# my_dac_amp_vB.net
KiCad netlist of a schematic drawn in EAGLE
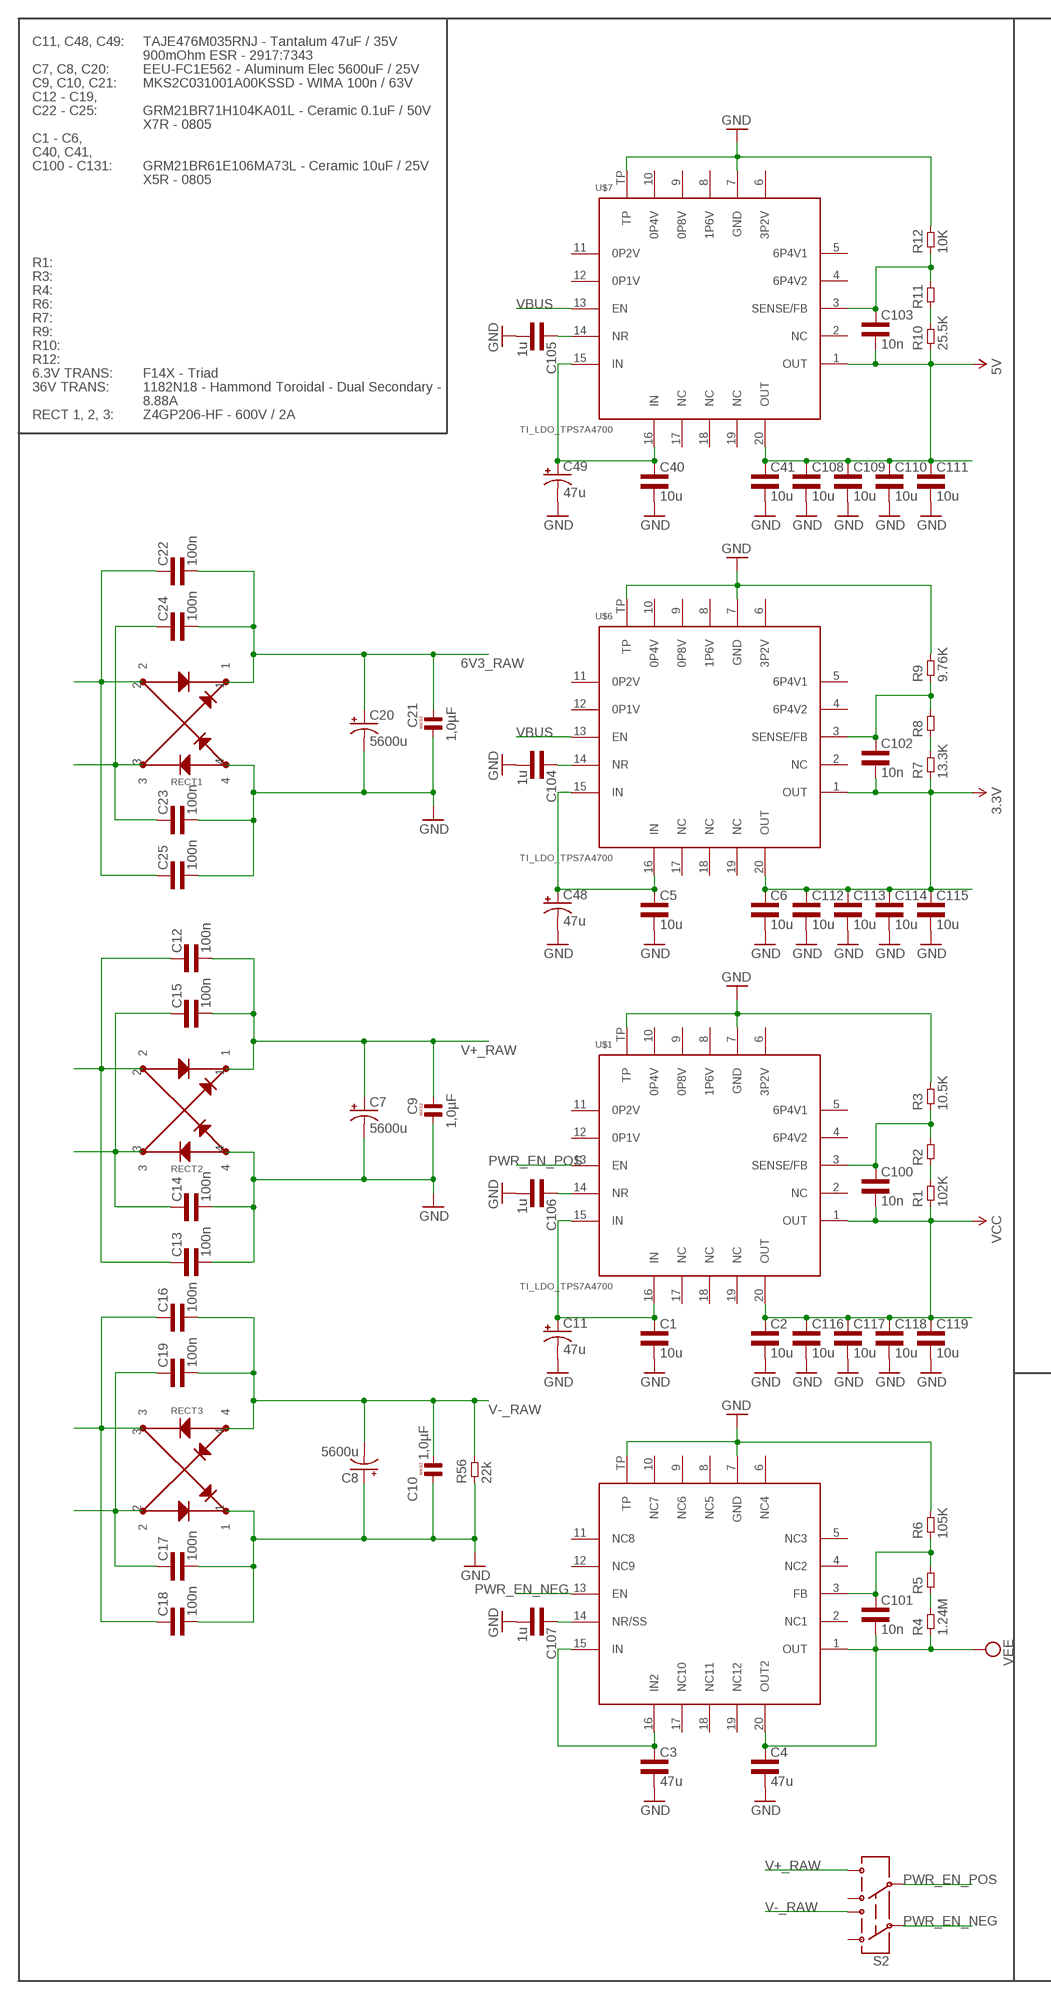
[diagram p0: schematic, sheet 1, part 1 of 2]
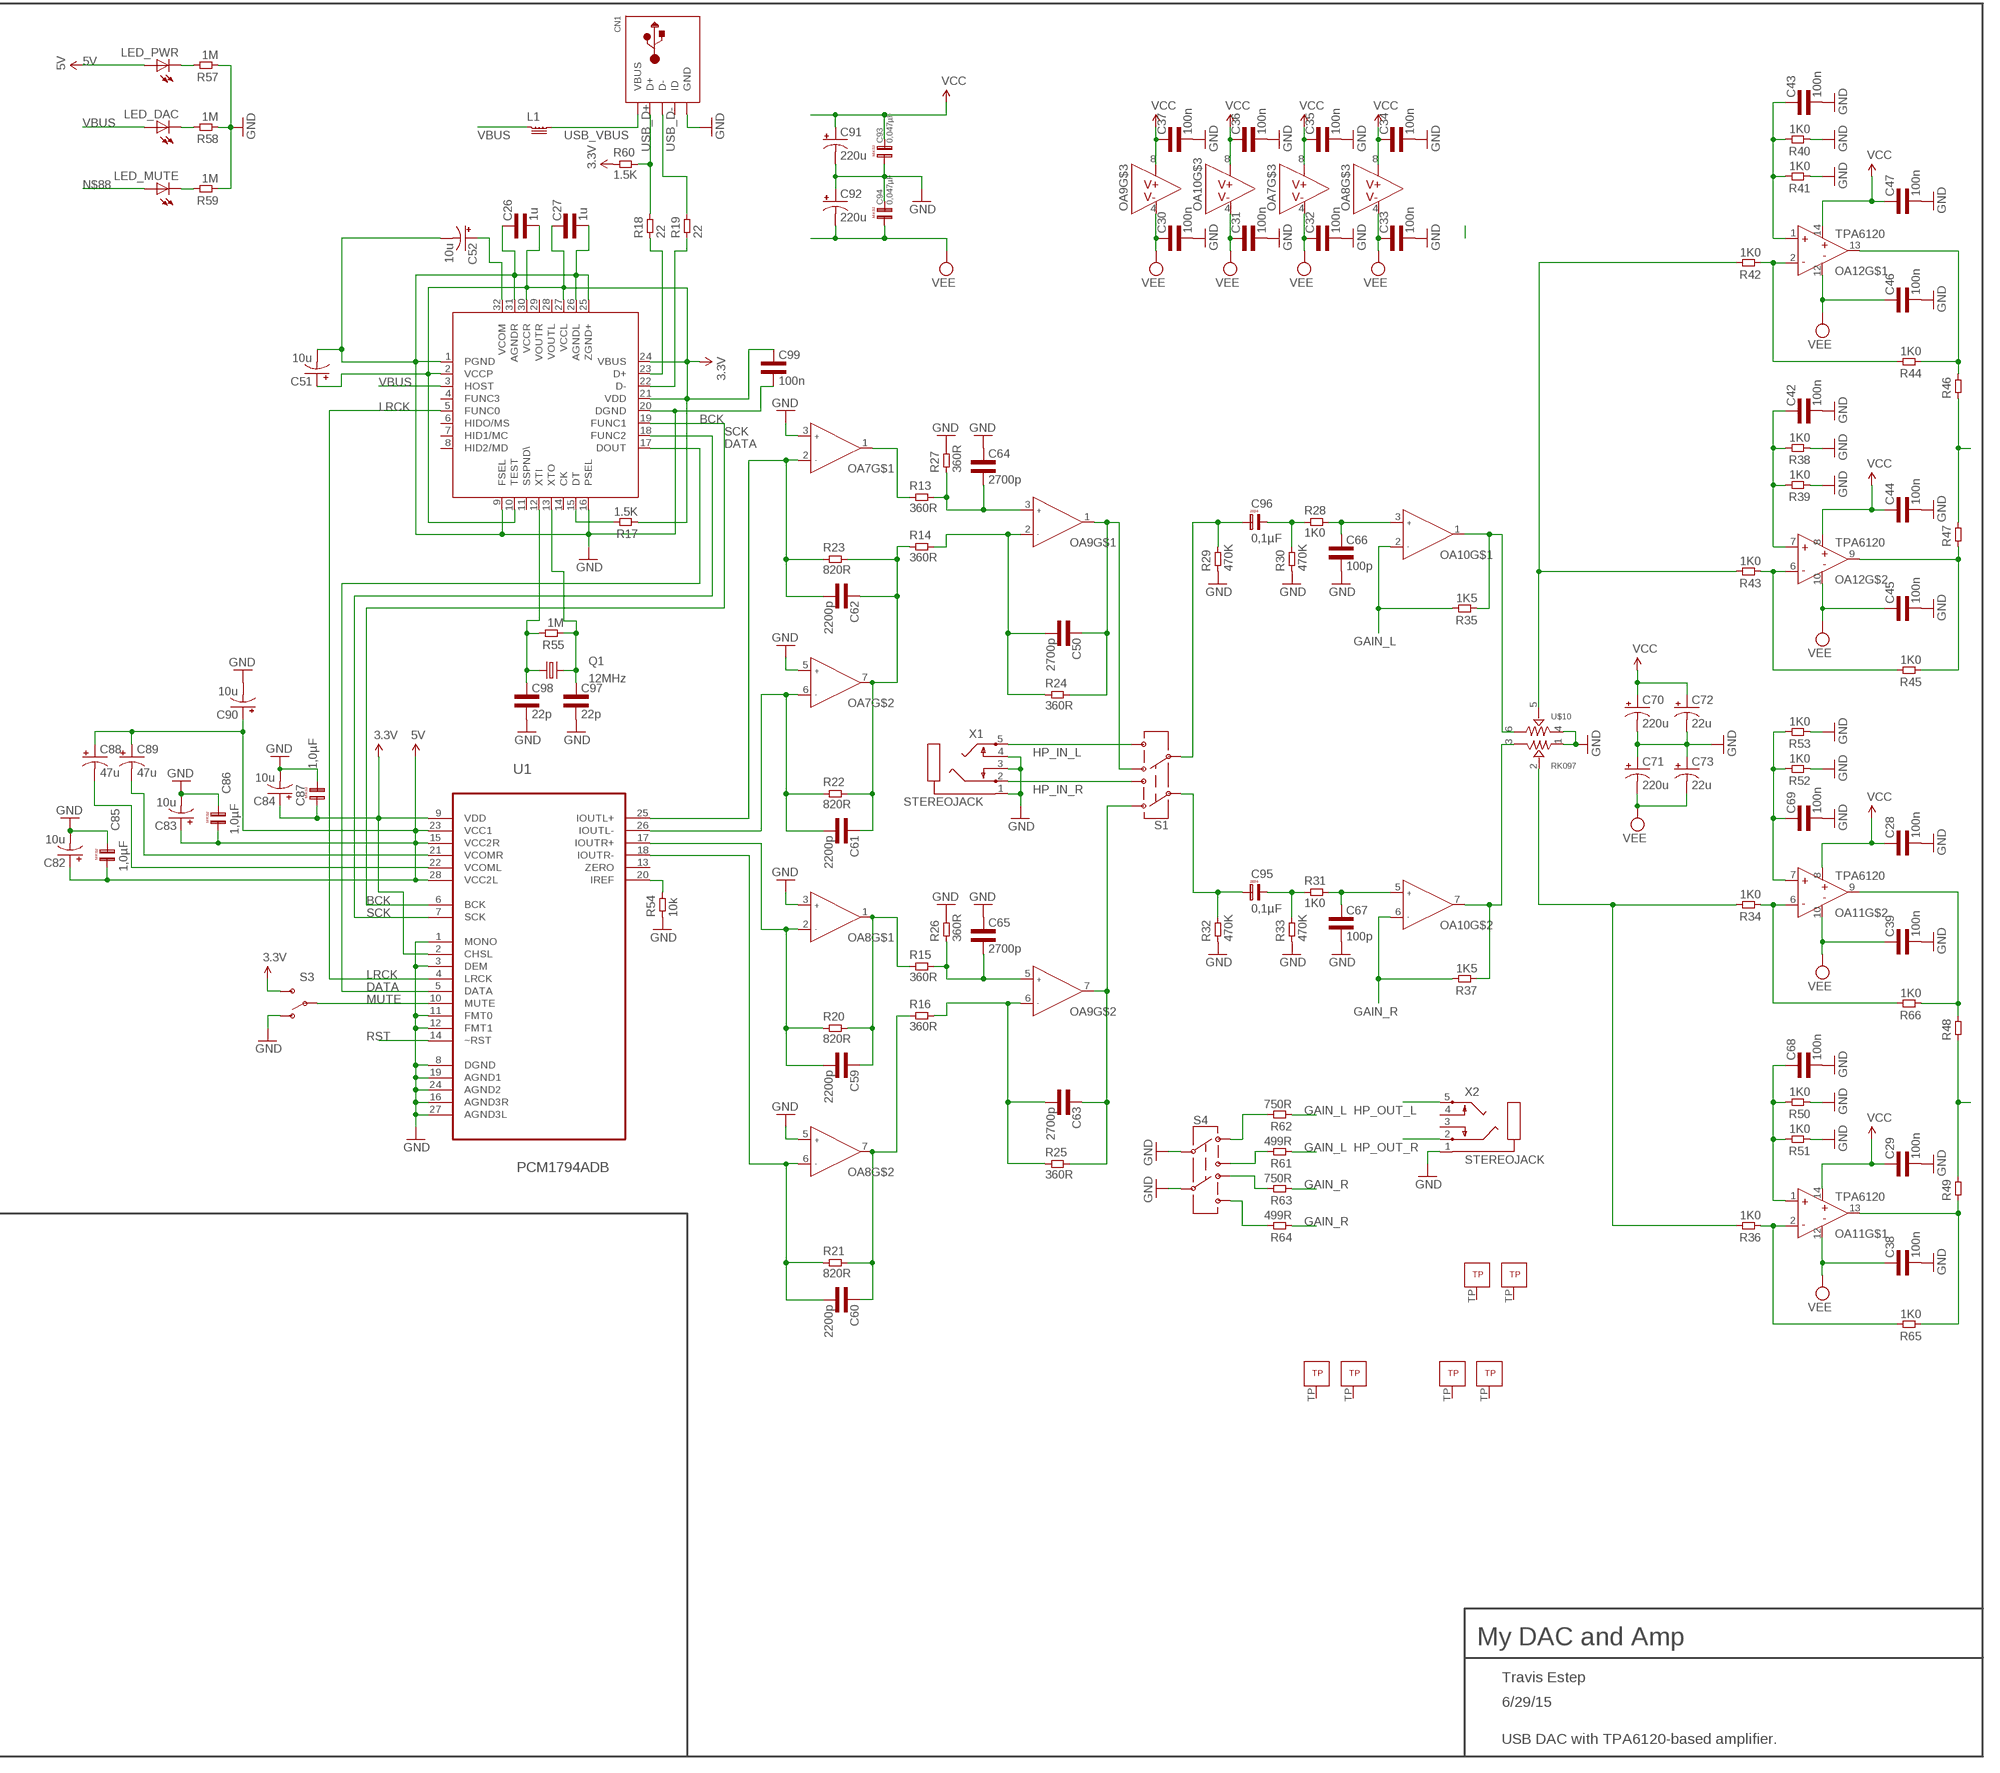
[diagram p1: schematic, sheet 1, part 2 of 2]

(export (version "E")
  (design (tool "Eeschema 10.0.6"))
  (components
    (comp (ref "C1")
      (value "10u")
      (footprint "eagle-import:1206L3")
      (libsource (lib "eagle-import") (part "CAP1206L3"))
    )
    (comp (ref "C2")
      (value "10u")
      (footprint "eagle-import:0805L3")
      (libsource (lib "eagle-import") (part "CAP0805L3"))
    )
    (comp (ref "C3")
      (value "47u")
      (footprint "eagle-import:1206L3")
      (libsource (lib "eagle-import") (part "CAP1206L3"))
    )
    (comp (ref "C4")
      (value "47u")
      (footprint "eagle-import:1206L3")
      (libsource (lib "eagle-import") (part "CAP1206L3"))
    )
    (comp (ref "C5")
      (value "10u")
      (footprint "eagle-import:1206L3")
      (libsource (lib "eagle-import") (part "CAP1206L3"))
    )
    (comp (ref "C6")
      (value "10u")
      (footprint "eagle-import:0805L3")
      (libsource (lib "eagle-import") (part "CAP0805L3"))
    )
    (comp (ref "C7")
      (value "5600u")
      (footprint "eagle-import:E7,5-16")
      (libsource (lib "eagle-import") (part "CPOL-USE7.5-16"))
    )
    (comp (ref "C8")
      (value "5600u")
      (footprint "eagle-import:E7,5-16")
      (libsource (lib "eagle-import") (part "CPOL-USE7.5-16"))
    )
    (comp (ref "C9")
      (value "1,0µF")
      (footprint "eagle-import:R5B5")
      (libsource (lib "eagle-import") (part "Capacitor-Wima-MKS2-63v_1,0µF"))
    )
    (comp (ref "C10")
      (value "1,0µF")
      (footprint "eagle-import:R5B5")
      (libsource (lib "eagle-import") (part "Capacitor-Wima-MKS2-63v_1,0µF"))
    )
    (comp (ref "C11")
      (value "47u")
      (footprint "eagle-import:SMC_E")
      (libsource (lib "eagle-import") (part "CPOL-USSMCE"))
    )
    (comp (ref "C12")
      (value "100n")
      (footprint "eagle-import:0805L3")
      (libsource (lib "eagle-import") (part "CAP0805L3"))
    )
    (comp (ref "C13")
      (value "100n")
      (footprint "eagle-import:0805L3")
      (libsource (lib "eagle-import") (part "CAP0805L3"))
    )
    (comp (ref "C14")
      (value "100n")
      (footprint "eagle-import:0805L3")
      (libsource (lib "eagle-import") (part "CAP0805L3"))
    )
    (comp (ref "C15")
      (value "100n")
      (footprint "eagle-import:0805L3")
      (libsource (lib "eagle-import") (part "CAP0805L3"))
    )
    (comp (ref "C16")
      (value "100n")
      (footprint "eagle-import:0805L3")
      (libsource (lib "eagle-import") (part "CAP0805L3"))
    )
    (comp (ref "C17")
      (value "100n")
      (footprint "eagle-import:0805L3")
      (libsource (lib "eagle-import") (part "CAP0805L3"))
    )
    (comp (ref "C18")
      (value "100n")
      (footprint "eagle-import:0805L3")
      (libsource (lib "eagle-import") (part "CAP0805L3"))
    )
    (comp (ref "C19")
      (value "100n")
      (footprint "eagle-import:0805L3")
      (libsource (lib "eagle-import") (part "CAP0805L3"))
    )
    (comp (ref "C20")
      (value "5600u")
      (footprint "eagle-import:E7,5-16")
      (libsource (lib "eagle-import") (part "CPOL-USE7.5-16"))
    )
    (comp (ref "C21")
      (value "1,0µF")
      (footprint "eagle-import:R5B5")
      (libsource (lib "eagle-import") (part "Capacitor-Wima-MKS2-63v_1,0µF"))
    )
    (comp (ref "C22")
      (value "100n")
      (footprint "eagle-import:0805L3")
      (libsource (lib "eagle-import") (part "CAP0805L3"))
    )
    (comp (ref "C23")
      (value "100n")
      (footprint "eagle-import:0805L3")
      (libsource (lib "eagle-import") (part "CAP0805L3"))
    )
    (comp (ref "C24")
      (value "100n")
      (footprint "eagle-import:0805L3")
      (libsource (lib "eagle-import") (part "CAP0805L3"))
    )
    (comp (ref "C25")
      (value "100n")
      (footprint "eagle-import:0805L3")
      (libsource (lib "eagle-import") (part "CAP0805L3"))
    )
    (comp (ref "C26")
      (value "1u")
      (footprint "eagle-import:0603L3")
      (libsource (lib "eagle-import") (part "CAP0603L3"))
    )
    (comp (ref "C27")
      (value "1u")
      (footprint "eagle-import:0603L3")
      (libsource (lib "eagle-import") (part "CAP0603L3"))
    )
    (comp (ref "C28")
      (value "100n")
      (footprint "eagle-import:0603L3")
      (libsource (lib "eagle-import") (part "CAP0603L3"))
    )
    (comp (ref "C29")
      (value "100n")
      (footprint "eagle-import:0603L3")
      (libsource (lib "eagle-import") (part "CAP0603L3"))
    )
    (comp (ref "C30")
      (value "100n")
      (footprint "eagle-import:0603L3")
      (libsource (lib "eagle-import") (part "CAP0603L3"))
    )
    (comp (ref "C31")
      (value "100n")
      (footprint "eagle-import:0603L3")
      (libsource (lib "eagle-import") (part "CAP0603L3"))
    )
    (comp (ref "C32")
      (value "100n")
      (footprint "eagle-import:0603L3")
      (libsource (lib "eagle-import") (part "CAP0603L3"))
    )
    (comp (ref "C33")
      (value "100n")
      (footprint "eagle-import:0603L3")
      (libsource (lib "eagle-import") (part "CAP0603L3"))
    )
    (comp (ref "C34")
      (value "100n")
      (footprint "eagle-import:0603L3")
      (libsource (lib "eagle-import") (part "CAP0603L3"))
    )
    (comp (ref "C35")
      (value "100n")
      (footprint "eagle-import:0603L3")
      (libsource (lib "eagle-import") (part "CAP0603L3"))
    )
    (comp (ref "C36")
      (value "100n")
      (footprint "eagle-import:0603L3")
      (libsource (lib "eagle-import") (part "CAP0603L3"))
    )
    (comp (ref "C37")
      (value "100n")
      (footprint "eagle-import:0603L3")
      (libsource (lib "eagle-import") (part "CAP0603L3"))
    )
    (comp (ref "C38")
      (value "100n")
      (footprint "eagle-import:0603L3")
      (libsource (lib "eagle-import") (part "CAP0603L3"))
    )
    (comp (ref "C39")
      (value "100n")
      (footprint "eagle-import:0603L3")
      (libsource (lib "eagle-import") (part "CAP0603L3"))
    )
    (comp (ref "C40")
      (value "10u")
      (footprint "eagle-import:1206L3")
      (libsource (lib "eagle-import") (part "CAP1206L3"))
    )
    (comp (ref "C41")
      (value "10u")
      (footprint "eagle-import:0805L3")
      (libsource (lib "eagle-import") (part "CAP0805L3"))
    )
    (comp (ref "C42")
      (value "100n")
      (footprint "eagle-import:0603L3")
      (libsource (lib "eagle-import") (part "CAP0603L3"))
    )
    (comp (ref "C43")
      (value "100n")
      (footprint "eagle-import:0603L3")
      (libsource (lib "eagle-import") (part "CAP0603L3"))
    )
    (comp (ref "C44")
      (value "100n")
      (footprint "eagle-import:0603L3")
      (libsource (lib "eagle-import") (part "CAP0603L3"))
    )
    (comp (ref "C45")
      (value "100n")
      (footprint "eagle-import:0603L3")
      (libsource (lib "eagle-import") (part "CAP0603L3"))
    )
    (comp (ref "C46")
      (value "100n")
      (footprint "eagle-import:0603L3")
      (libsource (lib "eagle-import") (part "CAP0603L3"))
    )
    (comp (ref "C47")
      (value "100n")
      (footprint "eagle-import:0603L3")
      (libsource (lib "eagle-import") (part "CAP0603L3"))
    )
    (comp (ref "C48")
      (value "47u")
      (footprint "eagle-import:SMC_E")
      (libsource (lib "eagle-import") (part "CPOL-USSMCE"))
    )
    (comp (ref "C49")
      (value "47u")
      (footprint "eagle-import:SMC_E")
      (libsource (lib "eagle-import") (part "CPOL-USSMCE"))
    )
    (comp (ref "C50")
      (value "2700p")
      (footprint "eagle-import:0603L3")
      (libsource (lib "eagle-import") (part "CAP0603L3"))
    )
    (comp (ref "C51")
      (value "10u")
      (footprint "eagle-import:E3,5-8")
      (libsource (lib "eagle-import") (part "CPOL-USE3.5-8"))
    )
    (comp (ref "C52")
      (value "10u")
      (footprint "eagle-import:E3,5-8")
      (libsource (lib "eagle-import") (part "CPOL-USE3.5-8"))
    )
    (comp (ref "C59")
      (value "2200p")
      (footprint "eagle-import:0603L3")
      (libsource (lib "eagle-import") (part "CAP0603L3"))
    )
    (comp (ref "C60")
      (value "2200p")
      (footprint "eagle-import:0603L3")
      (libsource (lib "eagle-import") (part "CAP0603L3"))
    )
    (comp (ref "C61")
      (value "2200p")
      (footprint "eagle-import:0603L3")
      (libsource (lib "eagle-import") (part "CAP0603L3"))
    )
    (comp (ref "C62")
      (value "2200p")
      (footprint "eagle-import:0603L3")
      (libsource (lib "eagle-import") (part "CAP0603L3"))
    )
    (comp (ref "C63")
      (value "2700p")
      (footprint "eagle-import:0603L3")
      (libsource (lib "eagle-import") (part "CAP0603L3"))
    )
    (comp (ref "C64")
      (value "2700p")
      (footprint "eagle-import:0603L3")
      (libsource (lib "eagle-import") (part "CAP0603L3"))
    )
    (comp (ref "C65")
      (value "2700p")
      (footprint "eagle-import:0603L3")
      (libsource (lib "eagle-import") (part "CAP0603L3"))
    )
    (comp (ref "C66")
      (value "100p")
      (footprint "eagle-import:0603L3")
      (libsource (lib "eagle-import") (part "CAP0603L3"))
    )
    (comp (ref "C67")
      (value "100p")
      (footprint "eagle-import:0603L3")
      (libsource (lib "eagle-import") (part "CAP0603L3"))
    )
    (comp (ref "C68")
      (value "100n")
      (footprint "eagle-import:0603L3")
      (libsource (lib "eagle-import") (part "CAP0603L3"))
    )
    (comp (ref "C69")
      (value "100n")
      (footprint "eagle-import:0603L3")
      (libsource (lib "eagle-import") (part "CAP0603L3"))
    )
    (comp (ref "C70")
      (value "220u")
      (footprint "eagle-import:E5-13")
      (libsource (lib "eagle-import") (part "CPOL-USE5-13"))
    )
    (comp (ref "C71")
      (value "220u")
      (footprint "eagle-import:E5-13")
      (libsource (lib "eagle-import") (part "CPOL-USE5-13"))
    )
    (comp (ref "C72")
      (value "22u")
      (footprint "eagle-import:E3,5-8")
      (libsource (lib "eagle-import") (part "CPOL-USE3.5-8"))
    )
    (comp (ref "C73")
      (value "22u")
      (footprint "eagle-import:E3,5-8")
      (libsource (lib "eagle-import") (part "CPOL-USE3.5-8"))
    )
    (comp (ref "C82")
      (value "10u")
      (footprint "eagle-import:E3,5-8")
      (libsource (lib "eagle-import") (part "CPOL-USE3.5-8"))
    )
    (comp (ref "C83")
      (value "10u")
      (footprint "eagle-import:E3,5-8")
      (libsource (lib "eagle-import") (part "CPOL-USE3.5-8"))
    )
    (comp (ref "C84")
      (value "10u")
      (footprint "eagle-import:E3,5-8")
      (libsource (lib "eagle-import") (part "CPOL-USE3.5-8"))
    )
    (comp (ref "C85")
      (value "1,0µF")
      (footprint "eagle-import:R5B5")
      (libsource (lib "eagle-import") (part "1,0µF"))
    )
    (comp (ref "C86")
      (value "1,0µF")
      (footprint "eagle-import:R5B5")
      (libsource (lib "eagle-import") (part "1,0µF"))
    )
    (comp (ref "C87")
      (value "1,0µF")
      (footprint "eagle-import:R5B5")
      (libsource (lib "eagle-import") (part "1,0µF"))
    )
    (comp (ref "C88")
      (value "47u")
      (footprint "eagle-import:E5-10,5")
      (libsource (lib "eagle-import") (part "CPOL-USE5-10.5"))
    )
    (comp (ref "C89")
      (value "47u")
      (footprint "eagle-import:E5-10,5")
      (libsource (lib "eagle-import") (part "CPOL-USE5-10.5"))
    )
    (comp (ref "C90")
      (value "10u")
      (footprint "eagle-import:E3,5-8")
      (libsource (lib "eagle-import") (part "CPOL-USE3.5-8"))
    )
    (comp (ref "C91")
      (value "220u")
      (footprint "eagle-import:E5-13")
      (libsource (lib "eagle-import") (part "CPOL-USE5-13"))
    )
    (comp (ref "C92")
      (value "220u")
      (footprint "eagle-import:E5-13")
      (libsource (lib "eagle-import") (part "CPOL-USE5-13"))
    )
    (comp (ref "C93")
      (value "0,047µF")
      (footprint "eagle-import:R5B2K5")
      (libsource (lib "eagle-import") (part "0,047µF"))
    )
    (comp (ref "C94")
      (value "0,047µF")
      (footprint "eagle-import:R5B2K5")
      (libsource (lib "eagle-import") (part "0,047µF"))
    )
    (comp (ref "C95")
      (value "0,1µF")
      (footprint "eagle-import:L7,2")
      (libsource (lib "eagle-import") (part "0,1µF"))
    )
    (comp (ref "C96")
      (value "0,1µF")
      (footprint "eagle-import:L7,2")
      (libsource (lib "eagle-import") (part "0,1µF"))
    )
    (comp (ref "C97")
      (value "22p")
      (footprint "eagle-import:0603L3")
      (libsource (lib "eagle-import") (part "CAP0603L3"))
    )
    (comp (ref "C98")
      (value "22p")
      (footprint "eagle-import:0603L3")
      (libsource (lib "eagle-import") (part "CAP0603L3"))
    )
    (comp (ref "C99")
      (value "100n")
      (footprint "eagle-import:0603L3")
      (libsource (lib "eagle-import") (part "CAP0603L3"))
    )
    (comp (ref "C100")
      (value "10n")
      (footprint "eagle-import:0603L3")
      (libsource (lib "eagle-import") (part "CAP0603L3"))
    )
    (comp (ref "C101")
      (value "10n")
      (footprint "eagle-import:0603L3")
      (libsource (lib "eagle-import") (part "CAP0603L3"))
    )
    (comp (ref "C102")
      (value "10n")
      (footprint "eagle-import:0603L3")
      (libsource (lib "eagle-import") (part "CAP0603L3"))
    )
    (comp (ref "C103")
      (value "10n")
      (footprint "eagle-import:0603L3")
      (libsource (lib "eagle-import") (part "CAP0603L3"))
    )
    (comp (ref "C104")
      (value "1u")
      (footprint "eagle-import:0603L3")
      (libsource (lib "eagle-import") (part "CAP0603L3"))
    )
    (comp (ref "C105")
      (value "1u")
      (footprint "eagle-import:0603L3")
      (libsource (lib "eagle-import") (part "CAP0603L3"))
    )
    (comp (ref "C106")
      (value "1u")
      (footprint "eagle-import:0603L3")
      (libsource (lib "eagle-import") (part "CAP0603L3"))
    )
    (comp (ref "C107")
      (value "1u")
      (footprint "eagle-import:0603L3")
      (libsource (lib "eagle-import") (part "CAP0603L3"))
    )
    (comp (ref "C108")
      (value "10u")
      (footprint "eagle-import:0805L3")
      (libsource (lib "eagle-import") (part "CAP0805L3"))
    )
    (comp (ref "C109")
      (value "10u")
      (footprint "eagle-import:0805L3")
      (libsource (lib "eagle-import") (part "CAP0805L3"))
    )
    (comp (ref "C110")
      (value "10u")
      (footprint "eagle-import:0805L3")
      (libsource (lib "eagle-import") (part "CAP0805L3"))
    )
    (comp (ref "C111")
      (value "10u")
      (footprint "eagle-import:0805L3")
      (libsource (lib "eagle-import") (part "CAP0805L3"))
    )
    (comp (ref "C112")
      (value "10u")
      (footprint "eagle-import:0805L3")
      (libsource (lib "eagle-import") (part "CAP0805L3"))
    )
    (comp (ref "C113")
      (value "10u")
      (footprint "eagle-import:0805L3")
      (libsource (lib "eagle-import") (part "CAP0805L3"))
    )
    (comp (ref "C114")
      (value "10u")
      (footprint "eagle-import:0805L3")
      (libsource (lib "eagle-import") (part "CAP0805L3"))
    )
    (comp (ref "C115")
      (value "10u")
      (footprint "eagle-import:0805L3")
      (libsource (lib "eagle-import") (part "CAP0805L3"))
    )
    (comp (ref "C116")
      (value "10u")
      (footprint "eagle-import:0805L3")
      (libsource (lib "eagle-import") (part "CAP0805L3"))
    )
    (comp (ref "C117")
      (value "10u")
      (footprint "eagle-import:0805L3")
      (libsource (lib "eagle-import") (part "CAP0805L3"))
    )
    (comp (ref "C118")
      (value "10u")
      (footprint "eagle-import:0805L3")
      (libsource (lib "eagle-import") (part "CAP0805L3"))
    )
    (comp (ref "C119")
      (value "10u")
      (footprint "eagle-import:0805L3")
      (libsource (lib "eagle-import") (part "CAP0805L3"))
    )
    (comp (ref "CN1")
      (value "USBMINIB")
      (footprint "eagle-import:USB-MINIB")
      (libsource (lib "eagle-import") (part "USBMINIB"))
    )
    (comp (ref "L1")
      (value "SRP4020")
      (footprint "eagle-import:4440")
      (libsource (lib "eagle-import") (part "SRP4020"))
    )
    (comp (ref "LED_DAC")
      (value "LED3MM")
      (footprint "eagle-import:LED3MM")
      (libsource (lib "eagle-import") (part "LED3MM"))
    )
    (comp (ref "LED_MUTE")
      (value "LED3MM")
      (footprint "eagle-import:LED3MM")
      (libsource (lib "eagle-import") (part "LED3MM"))
    )
    (comp (ref "LED_PWR")
      (value "LED3MM")
      (footprint "eagle-import:LED3MM")
      (libsource (lib "eagle-import") (part "LED3MM"))
    )
    (comp (ref "OA7")
      (value "OPA1612")
      (footprint "eagle-import:S-PWSON-N8")
      (libsource (lib "eagle-import") (part "OPA1612"))
    )
    (comp (ref "OA8")
      (value "OPA1612")
      (footprint "eagle-import:S-PWSON-N8")
      (libsource (lib "eagle-import") (part "OPA1612"))
    )
    (comp (ref "OA9")
      (value "OPA1612")
      (footprint "eagle-import:S-PWSON-N8")
      (libsource (lib "eagle-import") (part "OPA1612"))
    )
    (comp (ref "OA10")
      (value "OPA1612")
      (footprint "eagle-import:S-PWSON-N8")
      (libsource (lib "eagle-import") (part "OPA1612"))
    )
    (comp (ref "OA11")
      (value "TPA6120QFN")
      (footprint "eagle-import:S-PVQFN-N14")
      (libsource (lib "eagle-import") (part "TPA6120QFN"))
    )
    (comp (ref "OA12")
      (value "TPA6120QFN")
      (footprint "eagle-import:S-PVQFN-N14")
      (libsource (lib "eagle-import") (part "TPA6120QFN"))
    )
    (comp (ref "Q1")
      (value "12MHz")
      (footprint "eagle-import:SPARKFUN_HC49US")
      (libsource (lib "eagle-import") (part "SPARKFUN_CRYSTALHC49US"))
    )
    (comp (ref "R1")
      (value "102K")
      (footprint "eagle-import:0603L3")
      (libsource (lib "eagle-import") (part "RES0603L3"))
    )
    (comp (ref "R2")
      (value "RES0603L3")
      (footprint "eagle-import:0603L3")
      (libsource (lib "eagle-import") (part "RES0603L3"))
    )
    (comp (ref "R3")
      (value "10.5K")
      (footprint "eagle-import:0603L3")
      (libsource (lib "eagle-import") (part "RES0603L3"))
    )
    (comp (ref "R4")
      (value "1.24M")
      (footprint "eagle-import:0603L3")
      (libsource (lib "eagle-import") (part "RES0603L3"))
    )
    (comp (ref "R5")
      (value "RES0603L3")
      (footprint "eagle-import:0603L3")
      (libsource (lib "eagle-import") (part "RES0603L3"))
    )
    (comp (ref "R6")
      (value "105K")
      (footprint "eagle-import:0603L3")
      (libsource (lib "eagle-import") (part "RES0603L3"))
    )
    (comp (ref "R7")
      (value "13.3K")
      (footprint "eagle-import:0603L3")
      (libsource (lib "eagle-import") (part "RES0603L3"))
    )
    (comp (ref "R8")
      (value "RES0603L3")
      (footprint "eagle-import:0603L3")
      (libsource (lib "eagle-import") (part "RES0603L3"))
    )
    (comp (ref "R9")
      (value "9.76K")
      (footprint "eagle-import:0603L3")
      (libsource (lib "eagle-import") (part "RES0603L3"))
    )
    (comp (ref "R10")
      (value "25.5K")
      (footprint "eagle-import:0603L3")
      (libsource (lib "eagle-import") (part "RES0603L3"))
    )
    (comp (ref "R11")
      (value "RES0603L3")
      (footprint "eagle-import:0603L3")
      (libsource (lib "eagle-import") (part "RES0603L3"))
    )
    (comp (ref "R12")
      (value "10K")
      (footprint "eagle-import:0603L3")
      (libsource (lib "eagle-import") (part "RES0603L3"))
    )
    (comp (ref "R13")
      (value "360R")
      (footprint "eagle-import:0603L3")
      (libsource (lib "eagle-import") (part "RES0603L3"))
    )
    (comp (ref "R14")
      (value "360R")
      (footprint "eagle-import:0603L3")
      (libsource (lib "eagle-import") (part "RES0603L3"))
    )
    (comp (ref "R15")
      (value "360R")
      (footprint "eagle-import:0603L3")
      (libsource (lib "eagle-import") (part "RES0603L3"))
    )
    (comp (ref "R16")
      (value "360R")
      (footprint "eagle-import:0603L3")
      (libsource (lib "eagle-import") (part "RES0603L3"))
    )
    (comp (ref "R17")
      (value "1.5K")
      (footprint "eagle-import:0603L3")
      (libsource (lib "eagle-import") (part "RES0603L3"))
    )
    (comp (ref "R18")
      (value "22")
      (footprint "eagle-import:0603L3")
      (libsource (lib "eagle-import") (part "RES0603L3"))
    )
    (comp (ref "R19")
      (value "22")
      (footprint "eagle-import:0603L3")
      (libsource (lib "eagle-import") (part "RES0603L3"))
    )
    (comp (ref "R20")
      (value "820R")
      (footprint "eagle-import:0603L3")
      (libsource (lib "eagle-import") (part "RES0603L3"))
    )
    (comp (ref "R21")
      (value "820R")
      (footprint "eagle-import:0603L3")
      (libsource (lib "eagle-import") (part "RES0603L3"))
    )
    (comp (ref "R22")
      (value "820R")
      (footprint "eagle-import:0603L3")
      (libsource (lib "eagle-import") (part "RES0603L3"))
    )
    (comp (ref "R23")
      (value "820R")
      (footprint "eagle-import:0603L3")
      (libsource (lib "eagle-import") (part "RES0603L3"))
    )
    (comp (ref "R24")
      (value "360R")
      (footprint "eagle-import:0603L3")
      (libsource (lib "eagle-import") (part "RES0603L3"))
    )
    (comp (ref "R25")
      (value "360R")
      (footprint "eagle-import:0603L3")
      (libsource (lib "eagle-import") (part "RES0603L3"))
    )
    (comp (ref "R26")
      (value "360R")
      (footprint "eagle-import:0603L3")
      (libsource (lib "eagle-import") (part "RES0603L3"))
    )
    (comp (ref "R27")
      (value "360R")
      (footprint "eagle-import:0603L3")
      (libsource (lib "eagle-import") (part "RES0603L3"))
    )
    (comp (ref "R28")
      (value "1K0")
      (footprint "eagle-import:0603L3")
      (libsource (lib "eagle-import") (part "RES0603L3"))
    )
    (comp (ref "R29")
      (value "470K")
      (footprint "eagle-import:0603L3")
      (libsource (lib "eagle-import") (part "RES0603L3"))
    )
    (comp (ref "R30")
      (value "470K")
      (footprint "eagle-import:0603L3")
      (libsource (lib "eagle-import") (part "RES0603L3"))
    )
    (comp (ref "R31")
      (value "1K0")
      (footprint "eagle-import:0603L3")
      (libsource (lib "eagle-import") (part "RES0603L3"))
    )
    (comp (ref "R32")
      (value "470K")
      (footprint "eagle-import:0603L3")
      (libsource (lib "eagle-import") (part "RES0603L3"))
    )
    (comp (ref "R33")
      (value "470K")
      (footprint "eagle-import:0603L3")
      (libsource (lib "eagle-import") (part "RES0603L3"))
    )
    (comp (ref "R34")
      (value "1K0")
      (footprint "eagle-import:0603L3")
      (libsource (lib "eagle-import") (part "RES0603L3"))
    )
    (comp (ref "R35")
      (value "1K5")
      (footprint "eagle-import:0603L3")
      (libsource (lib "eagle-import") (part "RES0603L3"))
    )
    (comp (ref "R36")
      (value "1K0")
      (footprint "eagle-import:0603L3")
      (libsource (lib "eagle-import") (part "RES0603L3"))
    )
    (comp (ref "R37")
      (value "1K5")
      (footprint "eagle-import:0603L3")
      (libsource (lib "eagle-import") (part "RES0603L3"))
    )
    (comp (ref "R38")
      (value "1K0")
      (footprint "eagle-import:0603L3")
      (libsource (lib "eagle-import") (part "RES0603L3"))
    )
    (comp (ref "R39")
      (value "1K0")
      (footprint "eagle-import:0603L3")
      (libsource (lib "eagle-import") (part "RES0603L3"))
    )
    (comp (ref "R40")
      (value "1K0")
      (footprint "eagle-import:0603L3")
      (libsource (lib "eagle-import") (part "RES0603L3"))
    )
    (comp (ref "R41")
      (value "1K0")
      (footprint "eagle-import:0603L3")
      (libsource (lib "eagle-import") (part "RES0603L3"))
    )
    (comp (ref "R42")
      (value "1K0")
      (footprint "eagle-import:0603L3")
      (libsource (lib "eagle-import") (part "RES0603L3"))
    )
    (comp (ref "R43")
      (value "1K0")
      (footprint "eagle-import:0603L3")
      (libsource (lib "eagle-import") (part "RES0603L3"))
    )
    (comp (ref "R44")
      (value "1K0")
      (footprint "eagle-import:0603L3")
      (libsource (lib "eagle-import") (part "RES0603L3"))
    )
    (comp (ref "R45")
      (value "1K0")
      (footprint "eagle-import:0603L3")
      (libsource (lib "eagle-import") (part "RES0603L3"))
    )
    (comp (ref "R46")
      (value "RES1206L3")
      (footprint "eagle-import:1206L3")
      (libsource (lib "eagle-import") (part "RES1206L3"))
    )
    (comp (ref "R47")
      (value "RES1206L3")
      (footprint "eagle-import:1206L3")
      (libsource (lib "eagle-import") (part "RES1206L3"))
    )
    (comp (ref "R48")
      (value "RES1206L3")
      (footprint "eagle-import:1206L3")
      (libsource (lib "eagle-import") (part "RES1206L3"))
    )
    (comp (ref "R49")
      (value "RES1206L3")
      (footprint "eagle-import:1206L3")
      (libsource (lib "eagle-import") (part "RES1206L3"))
    )
    (comp (ref "R50")
      (value "1K0")
      (footprint "eagle-import:0603L3")
      (libsource (lib "eagle-import") (part "RES0603L3"))
    )
    (comp (ref "R51")
      (value "1K0")
      (footprint "eagle-import:0603L3")
      (libsource (lib "eagle-import") (part "RES0603L3"))
    )
    (comp (ref "R52")
      (value "1K0")
      (footprint "eagle-import:0603L3")
      (libsource (lib "eagle-import") (part "RES0603L3"))
    )
    (comp (ref "R53")
      (value "1K0")
      (footprint "eagle-import:0603L3")
      (libsource (lib "eagle-import") (part "RES0603L3"))
    )
    (comp (ref "R54")
      (value "10k")
      (footprint "eagle-import:0603L3")
      (libsource (lib "eagle-import") (part "RES0603L3"))
    )
    (comp (ref "R55")
      (value "1M")
      (footprint "eagle-import:0603L3")
      (libsource (lib "eagle-import") (part "RES0603L3"))
    )
    (comp (ref "R56")
      (value "22k")
      (footprint "eagle-import:0805L3")
      (libsource (lib "eagle-import") (part "RES0805L3"))
    )
    (comp (ref "R57")
      (value "1M")
      (footprint "eagle-import:0603L3")
      (libsource (lib "eagle-import") (part "RES0603L3"))
    )
    (comp (ref "R58")
      (value "1M")
      (footprint "eagle-import:0603L3")
      (libsource (lib "eagle-import") (part "RES0603L3"))
    )
    (comp (ref "R59")
      (value "1M")
      (footprint "eagle-import:0603L3")
      (libsource (lib "eagle-import") (part "RES0603L3"))
    )
    (comp (ref "R60")
      (value "1.5K")
      (footprint "eagle-import:0603L3")
      (libsource (lib "eagle-import") (part "RES0603L3"))
    )
    (comp (ref "R61")
      (value "499R")
      (footprint "eagle-import:0603L3")
      (libsource (lib "eagle-import") (part "RES0603L3"))
    )
    (comp (ref "R62")
      (value "750R")
      (footprint "eagle-import:0603L3")
      (libsource (lib "eagle-import") (part "RES0603L3"))
    )
    (comp (ref "R63")
      (value "750R")
      (footprint "eagle-import:0603L3")
      (libsource (lib "eagle-import") (part "RES0603L3"))
    )
    (comp (ref "R64")
      (value "499R")
      (footprint "eagle-import:0603L3")
      (libsource (lib "eagle-import") (part "RES0603L3"))
    )
    (comp (ref "R65")
      (value "1K0")
      (footprint "eagle-import:0603L3")
      (libsource (lib "eagle-import") (part "RES0603L3"))
    )
    (comp (ref "R66")
      (value "1K0")
      (footprint "eagle-import:0603L3")
      (libsource (lib "eagle-import") (part "RES0603L3"))
    )
    (comp (ref "RECT1")
      (value "Z4GP206")
      (footprint "eagle-import:ABS-4")
      (libsource (lib "eagle-import") (part "Z4GP206"))
    )
    (comp (ref "RECT2")
      (value "Z4GP206")
      (footprint "eagle-import:ABS-4")
      (libsource (lib "eagle-import") (part "Z4GP206"))
    )
    (comp (ref "RECT3")
      (value "Z4GP206")
      (footprint "eagle-import:ABS-4")
      (libsource (lib "eagle-import") (part "Z4GP206"))
    )
    (comp (ref "S1")
      (value "SWITCH-DPDTOS")
      (footprint "eagle-import:OS")
      (libsource (lib "eagle-import") (part "SWITCH-DPDTOS"))
    )
    (comp (ref "S2")
      (value "SWITCH-DPDTOS")
      (footprint "eagle-import:OS")
      (libsource (lib "eagle-import") (part "SWITCH-DPDTOS"))
    )
    (comp (ref "S3")
      (value "SWITCH-SPDTKIT")
      (footprint "eagle-import:SWITCH-SPDT_KIT")
      (libsource (lib "eagle-import") (part "SWITCH-SPDTKIT"))
    )
    (comp (ref "S4")
      (value "SWITCH-DPDTOS")
      (footprint "eagle-import:OS")
      (libsource (lib "eagle-import") (part "SWITCH-DPDTOS"))
    )
    (comp (ref "U$1")
      (value "TI_LDO_TPS7A4700")
      (footprint "eagle-import:TI_LDO_VQFN-20")
      (libsource (lib "eagle-import") (part "TI_LDO_TPS7A4700"))
    )
    (comp (ref "U$2")
      (value "TI_LDO_TPS7A3301RGWT")
      (footprint "eagle-import:TI_LDO_VQFN-20")
      (libsource (lib "eagle-import") (part "TI_LDO_TPS7A3301RGWT"))
    )
    (comp (ref "U$3")
      (value "PCM2704C_PCM2707")
      (footprint "eagle-import:PCM2704C_PCM2707")
      (libsource (lib "eagle-import") (part "PCM2704C_PCM2707"))
    )
    (comp (ref "U$6")
      (value "TI_LDO_TPS7A4700")
      (footprint "eagle-import:TI_LDO_VQFN-20")
      (libsource (lib "eagle-import") (part "TI_LDO_TPS7A4700"))
    )
    (comp (ref "U$7")
      (value "TI_LDO_TPS7A4700")
      (footprint "eagle-import:TI_LDO_VQFN-20")
      (libsource (lib "eagle-import") (part "TI_LDO_TPS7A4700"))
    )
    (comp (ref "U$10")
      (value "RK097")
      (footprint "eagle-import:RK097")
      (libsource (lib "eagle-import") (part "RK097"))
    )
    (comp (ref "U1")
      (value "PCM1794ADB")
      (footprint "eagle-import:SOP65P780X200-28N")
      (libsource (lib "eagle-import") (part "PCM1794ADB"))
    )
    (comp (ref "X1")
      (value "STEREOJACK")
      (footprint "eagle-import:STX3100")
      (libsource (lib "eagle-import") (part "STEREOJACK"))
    )
    (comp (ref "X2")
      (value "STEREOJACK")
      (footprint "eagle-import:STX3100")
      (libsource (lib "eagle-import") (part "STEREOJACK"))
    )
  )
  (nets
    (net (code "1") (name "/6V3_RAW") (class "Default")
      (node (ref "C20") (pin "+") (pinfunction "+_+") (pintype "passive"))
      (node (ref "C21") (pin "2") (pinfunction "2_2") (pintype "passive"))
      (node (ref "C22") (pin "2") (pinfunction "2_2") (pintype "bidirectional"))
      (node (ref "C24") (pin "2") (pinfunction "2_2") (pintype "bidirectional"))
      (node (ref "C40") (pin "1") (pinfunction "1_1") (pintype "bidirectional"))
      (node (ref "C48") (pin "+") (pinfunction "+_+") (pintype "passive"))
      (node (ref "C49") (pin "+") (pinfunction "+_+") (pintype "passive"))
      (node (ref "C5") (pin "1") (pinfunction "1_1") (pintype "bidirectional"))
      (node (ref "RECT1") (pin "1") (pinfunction "1_1") (pintype "bidirectional"))
      (node (ref "U$6") (pin "15") (pinfunction "IN_15") (pintype "bidirectional"))
      (node (ref "U$6") (pin "16") (pinfunction "IN_16") (pintype "bidirectional"))
      (node (ref "U$7") (pin "15") (pinfunction "IN_15") (pintype "bidirectional"))
      (node (ref "U$7") (pin "16") (pinfunction "IN_16") (pintype "bidirectional"))
    )
    (net (code "2") (name "/BCK") (class "Default")
      (node (ref "U$3") (pin "19") (pinfunction "FUNC1_19") (pintype "bidirectional"))
      (node (ref "U1") (pin "6") (pinfunction "BCK_6") (pintype "input"))
    )
    (net (code "3") (name "/DATA") (class "Default")
      (node (ref "U$3") (pin "17") (pinfunction "DOUT_17") (pintype "bidirectional"))
      (node (ref "U1") (pin "5") (pinfunction "DATA_5") (pintype "input"))
    )
    (net (code "4") (name "/GAIN_L") (class "Default")
      (node (ref "OA10") (pin "2") (pinfunction "INA-_2") (pintype "bidirectional"))
      (node (ref "R35") (pin "P$2") (pinfunction "2_P$2") (pintype "bidirectional"))
      (node (ref "R61") (pin "P$1") (pinfunction "1_P$1") (pintype "bidirectional"))
      (node (ref "R62") (pin "P$1") (pinfunction "1_P$1") (pintype "bidirectional"))
    )
    (net (code "5") (name "/GAIN_R") (class "Default")
      (node (ref "OA10") (pin "6") (pinfunction "INB-_6") (pintype "bidirectional"))
      (node (ref "R37") (pin "P$2") (pinfunction "2_P$2") (pintype "bidirectional"))
      (node (ref "R63") (pin "P$1") (pinfunction "1_P$1") (pintype "bidirectional"))
      (node (ref "R64") (pin "P$1") (pinfunction "1_P$1") (pintype "bidirectional"))
    )
    (net (code "6") (name "/HP_IN_L") (class "Default")
      (node (ref "S1") (pin "6") (pinfunction "6_6") (pintype "bidirectional"))
      (node (ref "X1") (pin "5") (pinfunction "5_5") (pintype "passive"))
    )
    (net (code "7") (name "/HP_IN_R") (class "Default")
      (node (ref "S1") (pin "3") (pinfunction "3_3") (pintype "bidirectional"))
      (node (ref "X1") (pin "2") (pinfunction "2_2") (pintype "passive"))
    )
    (net (code "8") (name "/HP_OUT_L") (class "Default")
      (node (ref "R46") (pin "1") (pinfunction "1_1") (pintype "bidirectional"))
      (node (ref "R47") (pin "2") (pinfunction "2_2") (pintype "bidirectional"))
      (node (ref "X2") (pin "5") (pinfunction "5_5") (pintype "passive"))
    )
    (net (code "9") (name "/HP_OUT_R") (class "Default")
      (node (ref "R48") (pin "1") (pinfunction "1_1") (pintype "bidirectional"))
      (node (ref "R49") (pin "2") (pinfunction "2_2") (pintype "bidirectional"))
      (node (ref "X2") (pin "2") (pinfunction "2_2") (pintype "passive"))
    )
    (net (code "10") (name "/LRCK") (class "Default")
      (node (ref "U$3") (pin "5") (pinfunction "FUNC0_5") (pintype "bidirectional"))
      (node (ref "U1") (pin "4") (pinfunction "LRCK_4") (pintype "input"))
    )
    (net (code "11") (name "/MUTE") (class "Default")
      (node (ref "S3") (pin "2") (pinfunction "P_2") (pintype "passive"))
      (node (ref "U1") (pin "10") (pinfunction "MUTE_10") (pintype "input"))
    )
    (net (code "12") (name "/N$88") (class "Default")
      (node (ref "LED_MUTE") (pin "A") (pinfunction "A_A") (pintype "passive"))
    )
    (net (code "13") (name "/PWR_EN_NEG") (class "Default")
      (node (ref "S2") (pin "2") (pinfunction "2_2") (pintype "bidirectional"))
      (node (ref "U$2") (pin "13") (pinfunction "EN_13") (pintype "bidirectional"))
    )
    (net (code "14") (name "/PWR_EN_POS") (class "Default")
      (node (ref "S2") (pin "5") (pinfunction "5_5") (pintype "bidirectional"))
      (node (ref "U$1") (pin "13") (pinfunction "EN_13") (pintype "bidirectional"))
    )
    (net (code "15") (name "/RST") (class "Default")
      (node (ref "U1") (pin "14") (pinfunction "~{RST}_14") (pintype "input"))
    )
    (net (code "16") (name "/SCK") (class "Default")
      (node (ref "U$3") (pin "18") (pinfunction "FUNC2_18") (pintype "bidirectional"))
      (node (ref "U1") (pin "7") (pinfunction "SCK_7") (pintype "input"))
    )
    (net (code "17") (name "/USB_D+") (class "Default")
      (node (ref "CN1") (pin "D+") (pinfunction "D+_D+") (pintype "bidirectional"))
      (node (ref "R18") (pin "P$2") (pinfunction "2_P$2") (pintype "bidirectional"))
      (node (ref "R60") (pin "P$2") (pinfunction "2_P$2") (pintype "bidirectional"))
    )
    (net (code "18") (name "/USB_D-") (class "Default")
      (node (ref "CN1") (pin "D-") (pinfunction "D-_D-") (pintype "bidirectional"))
      (node (ref "R19") (pin "P$2") (pinfunction "2_P$2") (pintype "bidirectional"))
    )
    (net (code "19") (name "/USB_VBUS") (class "Default")
      (node (ref "CN1") (pin "VBUS") (pinfunction "VBUS_VBUS") (pintype "power_in"))
      (node (ref "L1") (pin "2") (pinfunction "2_2") (pintype "bidirectional"))
    )
    (net (code "20") (name "/V+_RAW") (class "Default")
      (node (ref "C1") (pin "1") (pinfunction "1_1") (pintype "bidirectional"))
      (node (ref "C11") (pin "+") (pinfunction "+_+") (pintype "passive"))
      (node (ref "C12") (pin "2") (pinfunction "2_2") (pintype "bidirectional"))
      (node (ref "C15") (pin "2") (pinfunction "2_2") (pintype "bidirectional"))
      (node (ref "C7") (pin "+") (pinfunction "+_+") (pintype "passive"))
      (node (ref "C9") (pin "2") (pinfunction "2_2") (pintype "passive"))
      (node (ref "RECT2") (pin "1") (pinfunction "1_1") (pintype "bidirectional"))
      (node (ref "S2") (pin "6") (pinfunction "6_6") (pintype "bidirectional"))
      (node (ref "U$1") (pin "15") (pinfunction "IN_15") (pintype "bidirectional"))
      (node (ref "U$1") (pin "16") (pinfunction "IN_16") (pintype "bidirectional"))
    )
    (net (code "21") (name "/V-_RAW") (class "Default")
      (node (ref "C10") (pin "2") (pinfunction "2_2") (pintype "passive"))
      (node (ref "C16") (pin "2") (pinfunction "2_2") (pintype "bidirectional"))
      (node (ref "C19") (pin "2") (pinfunction "2_2") (pintype "bidirectional"))
      (node (ref "C3") (pin "1") (pinfunction "1_1") (pintype "bidirectional"))
      (node (ref "C8") (pin "-") (pinfunction "-_-") (pintype "passive"))
      (node (ref "R56") (pin "2") (pinfunction "2_2") (pintype "bidirectional"))
      (node (ref "RECT3") (pin "4") (pinfunction "4_4") (pintype "bidirectional"))
      (node (ref "S2") (pin "3") (pinfunction "3_3") (pintype "bidirectional"))
      (node (ref "U$2") (pin "15") (pinfunction "IN_15") (pintype "bidirectional"))
      (node (ref "U$2") (pin "16") (pinfunction "IN2_16") (pintype "bidirectional"))
    )
    (net (code "22") (name "/VBUS") (class "Default")
      (node (ref "L1") (pin "1") (pinfunction "1_1") (pintype "bidirectional"))
      (node (ref "LED_DAC") (pin "A") (pinfunction "A_A") (pintype "passive"))
      (node (ref "U$3") (pin "3") (pinfunction "HOST_3") (pintype "bidirectional"))
      (node (ref "U$6") (pin "13") (pinfunction "EN_13") (pintype "bidirectional"))
      (node (ref "U$7") (pin "13") (pinfunction "EN_13") (pintype "bidirectional"))
    )
    (net (code "23") (name "3.3V") (class "Default")
      (node (ref "C102") (pin "P$2") (pinfunction "2_P$2") (pintype "bidirectional"))
      (node (ref "C112") (pin "1") (pinfunction "1_1") (pintype "bidirectional"))
      (node (ref "C113") (pin "1") (pinfunction "1_1") (pintype "bidirectional"))
      (node (ref "C114") (pin "1") (pinfunction "1_1") (pintype "bidirectional"))
      (node (ref "C115") (pin "1") (pinfunction "1_1") (pintype "bidirectional"))
      (node (ref "C26") (pin "P$2") (pinfunction "2_P$2") (pintype "bidirectional"))
      (node (ref "C27") (pin "P$1") (pinfunction "1_P$1") (pintype "bidirectional"))
      (node (ref "C51") (pin "+") (pinfunction "+_+") (pintype "passive"))
      (node (ref "C6") (pin "1") (pinfunction "1_1") (pintype "bidirectional"))
      (node (ref "C84") (pin "+") (pinfunction "+_+") (pintype "passive"))
      (node (ref "C87") (pin "1") (pinfunction "1_1") (pintype "passive"))
      (node (ref "C99") (pin "P$1") (pinfunction "1_P$1") (pintype "bidirectional"))
      (node (ref "R17") (pin "P$1") (pinfunction "1_P$1") (pintype "bidirectional"))
      (node (ref "R60") (pin "P$1") (pinfunction "1_P$1") (pintype "bidirectional"))
      (node (ref "R7") (pin "P$1") (pinfunction "1_P$1") (pintype "bidirectional"))
      (node (ref "S3") (pin "3") (pinfunction "S_3") (pintype "passive"))
      (node (ref "U$3") (pin "10") (pinfunction "TEST_10") (pintype "bidirectional"))
      (node (ref "U$3") (pin "2") (pinfunction "VCCP_2") (pintype "bidirectional"))
      (node (ref "U$3") (pin "21") (pinfunction "VDD_21") (pintype "bidirectional"))
      (node (ref "U$3") (pin "24") (pinfunction "VBUS_24") (pintype "bidirectional"))
      (node (ref "U$3") (pin "27") (pinfunction "VCCL_27") (pintype "bidirectional"))
      (node (ref "U$3") (pin "30") (pinfunction "VCCR_30") (pintype "bidirectional"))
      (node (ref "U$6") (pin "1") (pinfunction "OUT_1") (pintype "bidirectional"))
      (node (ref "U$6") (pin "20") (pinfunction "OUT_20") (pintype "bidirectional"))
      (node (ref "U1") (pin "2") (pinfunction "CHSL_2") (pintype "input"))
      (node (ref "U1") (pin "9") (pinfunction "VDD_9") (pintype "power_in"))
    )
    (net (code "24") (name "5V") (class "Default")
      (node (ref "C103") (pin "P$2") (pinfunction "2_P$2") (pintype "bidirectional"))
      (node (ref "C108") (pin "1") (pinfunction "1_1") (pintype "bidirectional"))
      (node (ref "C109") (pin "1") (pinfunction "1_1") (pintype "bidirectional"))
      (node (ref "C110") (pin "1") (pinfunction "1_1") (pintype "bidirectional"))
      (node (ref "C111") (pin "1") (pinfunction "1_1") (pintype "bidirectional"))
      (node (ref "C41") (pin "1") (pinfunction "1_1") (pintype "bidirectional"))
      (node (ref "C82") (pin "+") (pinfunction "+_+") (pintype "passive"))
      (node (ref "C83") (pin "+") (pinfunction "+_+") (pintype "passive"))
      (node (ref "C85") (pin "1") (pinfunction "1_1") (pintype "passive"))
      (node (ref "C86") (pin "1") (pinfunction "1_1") (pintype "passive"))
      (node (ref "C88") (pin "+") (pinfunction "+_+") (pintype "passive"))
      (node (ref "C89") (pin "+") (pinfunction "+_+") (pintype "passive"))
      (node (ref "C90") (pin "+") (pinfunction "+_+") (pintype "passive"))
      (node (ref "LED_PWR") (pin "A") (pinfunction "A_A") (pintype "passive"))
      (node (ref "R10") (pin "P$1") (pinfunction "1_P$1") (pintype "bidirectional"))
      (node (ref "U$7") (pin "1") (pinfunction "OUT_1") (pintype "bidirectional"))
      (node (ref "U$7") (pin "20") (pinfunction "OUT_20") (pintype "bidirectional"))
      (node (ref "U1") (pin "15") (pinfunction "VCC2R_15") (pintype "power_in"))
      (node (ref "U1") (pin "23") (pinfunction "VCC1_23") (pintype "power_in"))
      (node (ref "U1") (pin "28") (pinfunction "VCC2L_28") (pintype "power_in"))
    )
    (net (code "25") (name "GND") (class "Default")
      (node (ref "C1") (pin "2") (pinfunction "2_2") (pintype "bidirectional"))
      (node (ref "C10") (pin "1") (pinfunction "1_1") (pintype "passive"))
      (node (ref "C104") (pin "P$2") (pinfunction "2_P$2") (pintype "bidirectional"))
      (node (ref "C105") (pin "P$2") (pinfunction "2_P$2") (pintype "bidirectional"))
      (node (ref "C106") (pin "P$2") (pinfunction "2_P$2") (pintype "bidirectional"))
      (node (ref "C107") (pin "P$2") (pinfunction "2_P$2") (pintype "bidirectional"))
      (node (ref "C108") (pin "2") (pinfunction "2_2") (pintype "bidirectional"))
      (node (ref "C109") (pin "2") (pinfunction "2_2") (pintype "bidirectional"))
      (node (ref "C11") (pin "-") (pinfunction "-_-") (pintype "passive"))
      (node (ref "C110") (pin "2") (pinfunction "2_2") (pintype "bidirectional"))
      (node (ref "C111") (pin "2") (pinfunction "2_2") (pintype "bidirectional"))
      (node (ref "C112") (pin "2") (pinfunction "2_2") (pintype "bidirectional"))
      (node (ref "C113") (pin "2") (pinfunction "2_2") (pintype "bidirectional"))
      (node (ref "C114") (pin "2") (pinfunction "2_2") (pintype "bidirectional"))
      (node (ref "C115") (pin "2") (pinfunction "2_2") (pintype "bidirectional"))
      (node (ref "C116") (pin "2") (pinfunction "2_2") (pintype "bidirectional"))
      (node (ref "C117") (pin "2") (pinfunction "2_2") (pintype "bidirectional"))
      (node (ref "C118") (pin "2") (pinfunction "2_2") (pintype "bidirectional"))
      (node (ref "C119") (pin "2") (pinfunction "2_2") (pintype "bidirectional"))
      (node (ref "C13") (pin "2") (pinfunction "2_2") (pintype "bidirectional"))
      (node (ref "C14") (pin "2") (pinfunction "2_2") (pintype "bidirectional"))
      (node (ref "C17") (pin "2") (pinfunction "2_2") (pintype "bidirectional"))
      (node (ref "C18") (pin "2") (pinfunction "2_2") (pintype "bidirectional"))
      (node (ref "C2") (pin "2") (pinfunction "2_2") (pintype "bidirectional"))
      (node (ref "C20") (pin "-") (pinfunction "-_-") (pintype "passive"))
      (node (ref "C21") (pin "1") (pinfunction "1_1") (pintype "passive"))
      (node (ref "C23") (pin "2") (pinfunction "2_2") (pintype "bidirectional"))
      (node (ref "C25") (pin "2") (pinfunction "2_2") (pintype "bidirectional"))
      (node (ref "C26") (pin "P$1") (pinfunction "1_P$1") (pintype "bidirectional"))
      (node (ref "C27") (pin "P$2") (pinfunction "2_P$2") (pintype "bidirectional"))
      (node (ref "C28") (pin "P$2") (pinfunction "2_P$2") (pintype "bidirectional"))
      (node (ref "C29") (pin "P$2") (pinfunction "2_P$2") (pintype "bidirectional"))
      (node (ref "C3") (pin "2") (pinfunction "2_2") (pintype "bidirectional"))
      (node (ref "C30") (pin "P$2") (pinfunction "2_P$2") (pintype "bidirectional"))
      (node (ref "C31") (pin "P$2") (pinfunction "2_P$2") (pintype "bidirectional"))
      (node (ref "C32") (pin "P$2") (pinfunction "2_P$2") (pintype "bidirectional"))
      (node (ref "C33") (pin "P$2") (pinfunction "2_P$2") (pintype "bidirectional"))
      (node (ref "C34") (pin "P$2") (pinfunction "2_P$2") (pintype "bidirectional"))
      (node (ref "C35") (pin "P$2") (pinfunction "2_P$2") (pintype "bidirectional"))
      (node (ref "C36") (pin "P$2") (pinfunction "2_P$2") (pintype "bidirectional"))
      (node (ref "C37") (pin "P$2") (pinfunction "2_P$2") (pintype "bidirectional"))
      (node (ref "C38") (pin "P$2") (pinfunction "2_P$2") (pintype "bidirectional"))
      (node (ref "C39") (pin "P$2") (pinfunction "2_P$2") (pintype "bidirectional"))
      (node (ref "C4") (pin "2") (pinfunction "2_2") (pintype "bidirectional"))
      (node (ref "C40") (pin "2") (pinfunction "2_2") (pintype "bidirectional"))
      (node (ref "C41") (pin "2") (pinfunction "2_2") (pintype "bidirectional"))
      (node (ref "C42") (pin "P$2") (pinfunction "2_P$2") (pintype "bidirectional"))
      (node (ref "C43") (pin "P$2") (pinfunction "2_P$2") (pintype "bidirectional"))
      (node (ref "C44") (pin "P$2") (pinfunction "2_P$2") (pintype "bidirectional"))
      (node (ref "C45") (pin "P$2") (pinfunction "2_P$2") (pintype "bidirectional"))
      (node (ref "C46") (pin "P$2") (pinfunction "2_P$2") (pintype "bidirectional"))
      (node (ref "C47") (pin "P$2") (pinfunction "2_P$2") (pintype "bidirectional"))
      (node (ref "C48") (pin "-") (pinfunction "-_-") (pintype "passive"))
      (node (ref "C49") (pin "-") (pinfunction "-_-") (pintype "passive"))
      (node (ref "C5") (pin "2") (pinfunction "2_2") (pintype "bidirectional"))
      (node (ref "C51") (pin "-") (pinfunction "-_-") (pintype "passive"))
      (node (ref "C52") (pin "-") (pinfunction "-_-") (pintype "passive"))
      (node (ref "C6") (pin "2") (pinfunction "2_2") (pintype "bidirectional"))
      (node (ref "C64") (pin "P$1") (pinfunction "1_P$1") (pintype "bidirectional"))
      (node (ref "C65") (pin "P$1") (pinfunction "1_P$1") (pintype "bidirectional"))
      (node (ref "C66") (pin "P$2") (pinfunction "2_P$2") (pintype "bidirectional"))
      (node (ref "C67") (pin "P$2") (pinfunction "2_P$2") (pintype "bidirectional"))
      (node (ref "C68") (pin "P$2") (pinfunction "2_P$2") (pintype "bidirectional"))
      (node (ref "C69") (pin "P$2") (pinfunction "2_P$2") (pintype "bidirectional"))
      (node (ref "C7") (pin "-") (pinfunction "-_-") (pintype "passive"))
      (node (ref "C70") (pin "-") (pinfunction "-_-") (pintype "passive"))
      (node (ref "C71") (pin "+") (pinfunction "+_+") (pintype "passive"))
      (node (ref "C72") (pin "-") (pinfunction "-_-") (pintype "passive"))
      (node (ref "C73") (pin "+") (pinfunction "+_+") (pintype "passive"))
      (node (ref "C8") (pin "+") (pinfunction "+_+") (pintype "passive"))
      (node (ref "C82") (pin "-") (pinfunction "-_-") (pintype "passive"))
      (node (ref "C83") (pin "-") (pinfunction "-_-") (pintype "passive"))
      (node (ref "C84") (pin "-") (pinfunction "-_-") (pintype "passive"))
      (node (ref "C85") (pin "2") (pinfunction "2_2") (pintype "passive"))
      (node (ref "C86") (pin "2") (pinfunction "2_2") (pintype "passive"))
      (node (ref "C87") (pin "2") (pinfunction "2_2") (pintype "passive"))
      (node (ref "C9") (pin "1") (pinfunction "1_1") (pintype "passive"))
      (node (ref "C90") (pin "-") (pinfunction "-_-") (pintype "passive"))
      (node (ref "C91") (pin "-") (pinfunction "-_-") (pintype "passive"))
      (node (ref "C92") (pin "+") (pinfunction "+_+") (pintype "passive"))
      (node (ref "C93") (pin "1") (pinfunction "1_1") (pintype "passive"))
      (node (ref "C94") (pin "2") (pinfunction "2_2") (pintype "passive"))
      (node (ref "C97") (pin "P$2") (pinfunction "2_P$2") (pintype "bidirectional"))
      (node (ref "C98") (pin "P$2") (pinfunction "2_P$2") (pintype "bidirectional"))
      (node (ref "C99") (pin "P$2") (pinfunction "2_P$2") (pintype "bidirectional"))
      (node (ref "CN1") (pin "GND") (pinfunction "GND_GND") (pintype "power_in"))
      (node (ref "OA7") (pin "3") (pinfunction "INA+_3") (pintype "bidirectional"))
      (node (ref "OA7") (pin "5") (pinfunction "INB+_5") (pintype "bidirectional"))
      (node (ref "OA8") (pin "3") (pinfunction "INA+_3") (pintype "bidirectional"))
      (node (ref "OA8") (pin "5") (pinfunction "INB+_5") (pintype "bidirectional"))
      (node (ref "R12") (pin "P$2") (pinfunction "2_P$2") (pintype "bidirectional"))
      (node (ref "R26") (pin "P$2") (pinfunction "2_P$2") (pintype "bidirectional"))
      (node (ref "R27") (pin "P$2") (pinfunction "2_P$2") (pintype "bidirectional"))
      (node (ref "R29") (pin "P$1") (pinfunction "1_P$1") (pintype "bidirectional"))
      (node (ref "R3") (pin "P$2") (pinfunction "2_P$2") (pintype "bidirectional"))
      (node (ref "R30") (pin "P$1") (pinfunction "1_P$1") (pintype "bidirectional"))
      (node (ref "R32") (pin "P$1") (pinfunction "1_P$1") (pintype "bidirectional"))
      (node (ref "R33") (pin "P$1") (pinfunction "1_P$1") (pintype "bidirectional"))
      (node (ref "R38") (pin "P$1") (pinfunction "1_P$1") (pintype "bidirectional"))
      (node (ref "R39") (pin "P$1") (pinfunction "1_P$1") (pintype "bidirectional"))
      (node (ref "R40") (pin "P$1") (pinfunction "1_P$1") (pintype "bidirectional"))
      (node (ref "R41") (pin "P$1") (pinfunction "1_P$1") (pintype "bidirectional"))
      (node (ref "R50") (pin "P$1") (pinfunction "1_P$1") (pintype "bidirectional"))
      (node (ref "R51") (pin "P$1") (pinfunction "1_P$1") (pintype "bidirectional"))
      (node (ref "R52") (pin "P$1") (pinfunction "1_P$1") (pintype "bidirectional"))
      (node (ref "R53") (pin "P$1") (pinfunction "1_P$1") (pintype "bidirectional"))
      (node (ref "R54") (pin "P$1") (pinfunction "1_P$1") (pintype "bidirectional"))
      (node (ref "R56") (pin "1") (pinfunction "1_1") (pintype "bidirectional"))
      (node (ref "R57") (pin "P$1") (pinfunction "1_P$1") (pintype "bidirectional"))
      (node (ref "R58") (pin "P$1") (pinfunction "1_P$1") (pintype "bidirectional"))
      (node (ref "R59") (pin "P$1") (pinfunction "1_P$1") (pintype "bidirectional"))
      (node (ref "R6") (pin "P$2") (pinfunction "2_P$2") (pintype "bidirectional"))
      (node (ref "R9") (pin "P$2") (pinfunction "2_P$2") (pintype "bidirectional"))
      (node (ref "RECT1") (pin "4") (pinfunction "4_4") (pintype "bidirectional"))
      (node (ref "RECT2") (pin "4") (pinfunction "4_4") (pintype "bidirectional"))
      (node (ref "RECT3") (pin "1") (pinfunction "1_1") (pintype "bidirectional"))
      (node (ref "S3") (pin "1") (pinfunction "O_1") (pintype "passive"))
      (node (ref "S4") (pin "2") (pinfunction "2_2") (pintype "bidirectional"))
      (node (ref "S4") (pin "5") (pinfunction "5_5") (pintype "bidirectional"))
      (node (ref "U$1") (pin "7") (pinfunction "GND_7") (pintype "bidirectional"))
      (node (ref "U$1") (pin "TP") (pinfunction "TP_TP") (pintype "bidirectional"))
      (node (ref "U$10") (pin "1") (pinfunction "1_1") (pintype "bidirectional"))
      (node (ref "U$10") (pin "4") (pinfunction "4_4") (pintype "bidirectional"))
      (node (ref "U$2") (pin "7") (pinfunction "GND_7") (pintype "bidirectional"))
      (node (ref "U$2") (pin "TP") (pinfunction "TP_TP") (pintype "bidirectional"))
      (node (ref "U$3") (pin "1") (pinfunction "PGND_1") (pintype "bidirectional"))
      (node (ref "U$3") (pin "16") (pinfunction "PSEL_16") (pintype "bidirectional"))
      (node (ref "U$3") (pin "20") (pinfunction "DGND_20") (pintype "bidirectional"))
      (node (ref "U$3") (pin "25") (pinfunction "ZGND+_25") (pintype "bidirectional"))
      (node (ref "U$3") (pin "26") (pinfunction "AGNDL_26") (pintype "bidirectional"))
      (node (ref "U$3") (pin "31") (pinfunction "AGNDR_31") (pintype "bidirectional"))
      (node (ref "U$3") (pin "9") (pinfunction "FSEL_9") (pintype "bidirectional"))
      (node (ref "U$6") (pin "7") (pinfunction "GND_7") (pintype "bidirectional"))
      (node (ref "U$6") (pin "TP") (pinfunction "TP_TP") (pintype "bidirectional"))
      (node (ref "U$7") (pin "7") (pinfunction "GND_7") (pintype "bidirectional"))
      (node (ref "U$7") (pin "TP") (pinfunction "TP_TP") (pintype "bidirectional"))
      (node (ref "U1") (pin "1") (pinfunction "MONO_1") (pintype "input"))
      (node (ref "U1") (pin "11") (pinfunction "FMT0_11") (pintype "input"))
      (node (ref "U1") (pin "12") (pinfunction "FMT1_12") (pintype "input"))
      (node (ref "U1") (pin "16") (pinfunction "AGND3R_16") (pintype "passive"))
      (node (ref "U1") (pin "19") (pinfunction "AGND1_19") (pintype "passive"))
      (node (ref "U1") (pin "24") (pinfunction "AGND2_24") (pintype "passive"))
      (node (ref "U1") (pin "27") (pinfunction "AGND3L_27") (pintype "passive"))
      (node (ref "U1") (pin "3") (pinfunction "DEM_3") (pintype "input"))
      (node (ref "U1") (pin "8") (pinfunction "DGND_8") (pintype "passive"))
      (node (ref "X1") (pin "1") (pinfunction "1_1") (pintype "passive"))
      (node (ref "X1") (pin "3") (pinfunction "3_3") (pintype "passive"))
      (node (ref "X1") (pin "4") (pinfunction "4_4") (pintype "passive"))
      (node (ref "X2") (pin "1") (pinfunction "1_1") (pintype "passive"))
    )
    (net (code "26") (name "Net-(C12-Pad1)") (class "Default")
      (node (ref "C12") (pin "1") (pinfunction "1_1") (pintype "bidirectional"))
      (node (ref "C13") (pin "1") (pinfunction "1_1") (pintype "bidirectional"))
      (node (ref "RECT2") (pin "2") (pinfunction "2_2") (pintype "bidirectional"))
    )
    (net (code "27") (name "Net-(C14-Pad1)") (class "Default")
      (node (ref "C14") (pin "1") (pinfunction "1_1") (pintype "bidirectional"))
      (node (ref "C15") (pin "1") (pinfunction "1_1") (pintype "bidirectional"))
      (node (ref "RECT2") (pin "3") (pinfunction "3_3") (pintype "bidirectional"))
    )
    (net (code "28") (name "Net-(C16-Pad1)") (class "Default")
      (node (ref "C16") (pin "1") (pinfunction "1_1") (pintype "bidirectional"))
      (node (ref "C18") (pin "1") (pinfunction "1_1") (pintype "bidirectional"))
      (node (ref "RECT3") (pin "3") (pinfunction "3_3") (pintype "bidirectional"))
    )
    (net (code "29") (name "Net-(C17-Pad1)") (class "Default")
      (node (ref "C17") (pin "1") (pinfunction "1_1") (pintype "bidirectional"))
      (node (ref "C19") (pin "1") (pinfunction "1_1") (pintype "bidirectional"))
      (node (ref "RECT3") (pin "2") (pinfunction "2_2") (pintype "bidirectional"))
    )
    (net (code "30") (name "Net-(C22-Pad1)") (class "Default")
      (node (ref "C22") (pin "1") (pinfunction "1_1") (pintype "bidirectional"))
      (node (ref "C25") (pin "1") (pinfunction "1_1") (pintype "bidirectional"))
      (node (ref "RECT1") (pin "2") (pinfunction "2_2") (pintype "bidirectional"))
    )
    (net (code "31") (name "Net-(C23-Pad1)") (class "Default")
      (node (ref "C23") (pin "1") (pinfunction "1_1") (pintype "bidirectional"))
      (node (ref "C24") (pin "1") (pinfunction "1_1") (pintype "bidirectional"))
      (node (ref "RECT1") (pin "3") (pinfunction "3_3") (pintype "bidirectional"))
    )
    (net (code "32") (name "Net-(C42-1)") (class "Default")
      (node (ref "C42") (pin "P$1") (pinfunction "1_P$1") (pintype "bidirectional"))
      (node (ref "OA12") (pin "7") (pinfunction "IN+_7") (pintype "bidirectional"))
      (node (ref "R38") (pin "P$2") (pinfunction "2_P$2") (pintype "bidirectional"))
      (node (ref "R39") (pin "P$2") (pinfunction "2_P$2") (pintype "bidirectional"))
    )
    (net (code "33") (name "Net-(C43-1)") (class "Default")
      (node (ref "C43") (pin "P$1") (pinfunction "1_P$1") (pintype "bidirectional"))
      (node (ref "OA12") (pin "1") (pinfunction "IN+_1") (pintype "bidirectional"))
      (node (ref "R40") (pin "P$2") (pinfunction "2_P$2") (pintype "bidirectional"))
      (node (ref "R41") (pin "P$2") (pinfunction "2_P$2") (pintype "bidirectional"))
    )
    (net (code "34") (name "Net-(C50-1)") (class "Default")
      (node (ref "C50") (pin "P$1") (pinfunction "1_P$1") (pintype "bidirectional"))
      (node (ref "OA9") (pin "1") (pinfunction "OUTA_1") (pintype "bidirectional"))
      (node (ref "R24") (pin "P$2") (pinfunction "2_P$2") (pintype "bidirectional"))
      (node (ref "S1") (pin "4") (pinfunction "4_4") (pintype "bidirectional"))
    )
    (net (code "35") (name "Net-(C50-2)") (class "Default")
      (node (ref "C50") (pin "P$2") (pinfunction "2_P$2") (pintype "bidirectional"))
      (node (ref "OA9") (pin "2") (pinfunction "INA-_2") (pintype "bidirectional"))
      (node (ref "R14") (pin "P$2") (pinfunction "2_P$2") (pintype "bidirectional"))
      (node (ref "R24") (pin "P$1") (pinfunction "1_P$1") (pintype "bidirectional"))
    )
    (net (code "36") (name "Net-(C59-1)") (class "Default")
      (node (ref "C59") (pin "P$1") (pinfunction "1_P$1") (pintype "bidirectional"))
      (node (ref "OA8") (pin "1") (pinfunction "OUTA_1") (pintype "bidirectional"))
      (node (ref "R15") (pin "P$1") (pinfunction "1_P$1") (pintype "bidirectional"))
      (node (ref "R20") (pin "P$2") (pinfunction "2_P$2") (pintype "bidirectional"))
    )
    (net (code "37") (name "Net-(C59-2)") (class "Default")
      (node (ref "C59") (pin "P$2") (pinfunction "2_P$2") (pintype "bidirectional"))
      (node (ref "OA8") (pin "2") (pinfunction "INA-_2") (pintype "bidirectional"))
      (node (ref "R20") (pin "P$1") (pinfunction "1_P$1") (pintype "bidirectional"))
      (node (ref "U1") (pin "17") (pinfunction "IOUTR+_17") (pintype "output"))
    )
    (net (code "38") (name "Net-(C60-1)") (class "Default")
      (node (ref "C60") (pin "P$1") (pinfunction "1_P$1") (pintype "bidirectional"))
      (node (ref "OA8") (pin "7") (pinfunction "OUTB_7") (pintype "bidirectional"))
      (node (ref "R16") (pin "P$1") (pinfunction "1_P$1") (pintype "bidirectional"))
      (node (ref "R21") (pin "P$2") (pinfunction "2_P$2") (pintype "bidirectional"))
    )
    (net (code "39") (name "Net-(C60-2)") (class "Default")
      (node (ref "C60") (pin "P$2") (pinfunction "2_P$2") (pintype "bidirectional"))
      (node (ref "OA8") (pin "6") (pinfunction "INB-_6") (pintype "bidirectional"))
      (node (ref "R21") (pin "P$1") (pinfunction "1_P$1") (pintype "bidirectional"))
      (node (ref "U1") (pin "18") (pinfunction "IOUTR-_18") (pintype "output"))
    )
    (net (code "40") (name "Net-(C61-1)") (class "Default")
      (node (ref "C61") (pin "P$1") (pinfunction "1_P$1") (pintype "bidirectional"))
      (node (ref "C62") (pin "P$1") (pinfunction "1_P$1") (pintype "bidirectional"))
      (node (ref "OA7") (pin "7") (pinfunction "OUTB_7") (pintype "bidirectional"))
      (node (ref "R14") (pin "P$1") (pinfunction "1_P$1") (pintype "bidirectional"))
      (node (ref "R22") (pin "P$2") (pinfunction "2_P$2") (pintype "bidirectional"))
      (node (ref "R23") (pin "P$2") (pinfunction "2_P$2") (pintype "bidirectional"))
    )
    (net (code "41") (name "Net-(C61-2)") (class "Default")
      (node (ref "C61") (pin "P$2") (pinfunction "2_P$2") (pintype "bidirectional"))
      (node (ref "OA7") (pin "6") (pinfunction "INB-_6") (pintype "bidirectional"))
      (node (ref "R22") (pin "P$1") (pinfunction "1_P$1") (pintype "bidirectional"))
      (node (ref "U1") (pin "26") (pinfunction "IOUTL-_26") (pintype "output"))
    )
    (net (code "42") (name "Net-(C62-2)") (class "Default")
      (node (ref "C62") (pin "P$2") (pinfunction "2_P$2") (pintype "bidirectional"))
      (node (ref "OA7") (pin "2") (pinfunction "INA-_2") (pintype "bidirectional"))
      (node (ref "R23") (pin "P$1") (pinfunction "1_P$1") (pintype "bidirectional"))
      (node (ref "U1") (pin "25") (pinfunction "IOUTL+_25") (pintype "output"))
    )
    (net (code "43") (name "Net-(C63-1)") (class "Default")
      (node (ref "C63") (pin "P$1") (pinfunction "1_P$1") (pintype "bidirectional"))
      (node (ref "OA9") (pin "7") (pinfunction "OUTB_7") (pintype "bidirectional"))
      (node (ref "R25") (pin "P$2") (pinfunction "2_P$2") (pintype "bidirectional"))
      (node (ref "S1") (pin "1") (pinfunction "1_1") (pintype "bidirectional"))
    )
    (net (code "44") (name "Net-(C63-2)") (class "Default")
      (node (ref "C63") (pin "P$2") (pinfunction "2_P$2") (pintype "bidirectional"))
      (node (ref "OA9") (pin "6") (pinfunction "INB-_6") (pintype "bidirectional"))
      (node (ref "R16") (pin "P$2") (pinfunction "2_P$2") (pintype "bidirectional"))
      (node (ref "R25") (pin "P$1") (pinfunction "1_P$1") (pintype "bidirectional"))
    )
    (net (code "45") (name "Net-(C64-2)") (class "Default")
      (node (ref "C64") (pin "P$2") (pinfunction "2_P$2") (pintype "bidirectional"))
      (node (ref "OA9") (pin "3") (pinfunction "INA+_3") (pintype "bidirectional"))
      (node (ref "R13") (pin "P$2") (pinfunction "2_P$2") (pintype "bidirectional"))
      (node (ref "R27") (pin "P$1") (pinfunction "1_P$1") (pintype "bidirectional"))
    )
    (net (code "46") (name "Net-(C65-2)") (class "Default")
      (node (ref "C65") (pin "P$2") (pinfunction "2_P$2") (pintype "bidirectional"))
      (node (ref "OA9") (pin "5") (pinfunction "INB+_5") (pintype "bidirectional"))
      (node (ref "R15") (pin "P$2") (pinfunction "2_P$2") (pintype "bidirectional"))
      (node (ref "R26") (pin "P$1") (pinfunction "1_P$1") (pintype "bidirectional"))
    )
    (net (code "47") (name "Net-(C66-1)") (class "Default")
      (node (ref "C66") (pin "P$1") (pinfunction "1_P$1") (pintype "bidirectional"))
      (node (ref "OA10") (pin "3") (pinfunction "INA+_3") (pintype "bidirectional"))
      (node (ref "R28") (pin "P$2") (pinfunction "2_P$2") (pintype "bidirectional"))
    )
    (net (code "48") (name "Net-(C67-1)") (class "Default")
      (node (ref "C67") (pin "P$1") (pinfunction "1_P$1") (pintype "bidirectional"))
      (node (ref "OA10") (pin "5") (pinfunction "INB+_5") (pintype "bidirectional"))
      (node (ref "R31") (pin "P$2") (pinfunction "2_P$2") (pintype "bidirectional"))
    )
    (net (code "49") (name "Net-(C68-1)") (class "Default")
      (node (ref "C68") (pin "P$1") (pinfunction "1_P$1") (pintype "bidirectional"))
      (node (ref "OA11") (pin "1") (pinfunction "IN+_1") (pintype "bidirectional"))
      (node (ref "R50") (pin "P$2") (pinfunction "2_P$2") (pintype "bidirectional"))
      (node (ref "R51") (pin "P$2") (pinfunction "2_P$2") (pintype "bidirectional"))
    )
    (net (code "50") (name "Net-(C69-1)") (class "Default")
      (node (ref "C69") (pin "P$1") (pinfunction "1_P$1") (pintype "bidirectional"))
      (node (ref "OA11") (pin "7") (pinfunction "IN+_7") (pintype "bidirectional"))
      (node (ref "R52") (pin "P$2") (pinfunction "2_P$2") (pintype "bidirectional"))
      (node (ref "R53") (pin "P$2") (pinfunction "2_P$2") (pintype "bidirectional"))
    )
    (net (code "51") (name "Net-(C95-1)") (class "Default")
      (node (ref "C95") (pin "P$1") (pinfunction "1_P$1") (pintype "passive"))
      (node (ref "R32") (pin "P$2") (pinfunction "2_P$2") (pintype "bidirectional"))
      (node (ref "S1") (pin "2") (pinfunction "2_2") (pintype "bidirectional"))
    )
    (net (code "52") (name "Net-(C95-2)") (class "Default")
      (node (ref "C95") (pin "P$2") (pinfunction "2_P$2") (pintype "passive"))
      (node (ref "R31") (pin "P$1") (pinfunction "1_P$1") (pintype "bidirectional"))
      (node (ref "R33") (pin "P$2") (pinfunction "2_P$2") (pintype "bidirectional"))
    )
    (net (code "53") (name "Net-(C96-1)") (class "Default")
      (node (ref "C96") (pin "P$1") (pinfunction "1_P$1") (pintype "passive"))
      (node (ref "R29") (pin "P$2") (pinfunction "2_P$2") (pintype "bidirectional"))
      (node (ref "S1") (pin "5") (pinfunction "5_5") (pintype "bidirectional"))
    )
    (net (code "54") (name "Net-(C96-2)") (class "Default")
      (node (ref "C96") (pin "P$2") (pinfunction "2_P$2") (pintype "passive"))
      (node (ref "R28") (pin "P$1") (pinfunction "1_P$1") (pintype "bidirectional"))
      (node (ref "R30") (pin "P$2") (pinfunction "2_P$2") (pintype "bidirectional"))
    )
    (net (code "55") (name "Net-(C97-1)") (class "Default")
      (node (ref "C97") (pin "P$1") (pinfunction "1_P$1") (pintype "bidirectional"))
      (node (ref "Q1") (pin "2") (pinfunction "2_2") (pintype "passive"))
      (node (ref "R55") (pin "P$1") (pinfunction "1_P$1") (pintype "bidirectional"))
      (node (ref "U$3") (pin "13") (pinfunction "XTO_13") (pintype "bidirectional"))
    )
    (net (code "56") (name "Net-(C98-1)") (class "Default")
      (node (ref "C98") (pin "P$1") (pinfunction "1_P$1") (pintype "bidirectional"))
      (node (ref "Q1") (pin "1") (pinfunction "1_1") (pintype "passive"))
      (node (ref "R55") (pin "P$2") (pinfunction "2_P$2") (pintype "bidirectional"))
      (node (ref "U$3") (pin "12") (pinfunction "XTI_12") (pintype "bidirectional"))
    )
    (net (code "57") (name "Net-(C100-1)") (class "Default")
      (node (ref "C100") (pin "P$1") (pinfunction "1_P$1") (pintype "bidirectional"))
      (node (ref "R2") (pin "P$2") (pinfunction "2_P$2") (pintype "bidirectional"))
      (node (ref "R3") (pin "P$1") (pinfunction "1_P$1") (pintype "bidirectional"))
      (node (ref "U$1") (pin "3") (pinfunction "SENSE/FB_3") (pintype "bidirectional"))
    )
    (net (code "58") (name "Net-(C101-1)") (class "Default")
      (node (ref "C101") (pin "P$1") (pinfunction "1_P$1") (pintype "bidirectional"))
      (node (ref "R5") (pin "P$2") (pinfunction "2_P$2") (pintype "bidirectional"))
      (node (ref "R6") (pin "P$1") (pinfunction "1_P$1") (pintype "bidirectional"))
      (node (ref "U$2") (pin "3") (pinfunction "FB_3") (pintype "bidirectional"))
    )
    (net (code "59") (name "Net-(C102-1)") (class "Default")
      (node (ref "C102") (pin "P$1") (pinfunction "1_P$1") (pintype "bidirectional"))
      (node (ref "R8") (pin "P$2") (pinfunction "2_P$2") (pintype "bidirectional"))
      (node (ref "R9") (pin "P$1") (pinfunction "1_P$1") (pintype "bidirectional"))
      (node (ref "U$6") (pin "3") (pinfunction "SENSE/FB_3") (pintype "bidirectional"))
    )
    (net (code "60") (name "Net-(C103-1)") (class "Default")
      (node (ref "C103") (pin "P$1") (pinfunction "1_P$1") (pintype "bidirectional"))
      (node (ref "R11") (pin "P$2") (pinfunction "2_P$2") (pintype "bidirectional"))
      (node (ref "R12") (pin "P$1") (pinfunction "1_P$1") (pintype "bidirectional"))
      (node (ref "U$7") (pin "3") (pinfunction "SENSE/FB_3") (pintype "bidirectional"))
    )
    (net (code "61") (name "Net-(C104-1)") (class "Default")
      (node (ref "C104") (pin "P$1") (pinfunction "1_P$1") (pintype "bidirectional"))
      (node (ref "U$6") (pin "14") (pinfunction "NR_14") (pintype "bidirectional"))
    )
    (net (code "62") (name "Net-(C105-1)") (class "Default")
      (node (ref "C105") (pin "P$1") (pinfunction "1_P$1") (pintype "bidirectional"))
      (node (ref "U$7") (pin "14") (pinfunction "NR_14") (pintype "bidirectional"))
    )
    (net (code "63") (name "Net-(C106-1)") (class "Default")
      (node (ref "C106") (pin "P$1") (pinfunction "1_P$1") (pintype "bidirectional"))
      (node (ref "U$1") (pin "14") (pinfunction "NR_14") (pintype "bidirectional"))
    )
    (net (code "64") (name "Net-(C107-1)") (class "Default")
      (node (ref "C107") (pin "P$1") (pinfunction "1_P$1") (pintype "bidirectional"))
      (node (ref "U$2") (pin "14") (pinfunction "NR/SS_14") (pintype "bidirectional"))
    )
    (net (code "65") (name "Net-(LED_DAC-C)") (class "Default")
      (node (ref "LED_DAC") (pin "K") (pinfunction "C_K") (pintype "passive"))
      (node (ref "R58") (pin "P$2") (pinfunction "2_P$2") (pintype "bidirectional"))
    )
    (net (code "66") (name "Net-(LED_MUTE-C)") (class "Default")
      (node (ref "LED_MUTE") (pin "K") (pinfunction "C_K") (pintype "passive"))
      (node (ref "R59") (pin "P$2") (pinfunction "2_P$2") (pintype "bidirectional"))
    )
    (net (code "67") (name "Net-(LED_PWR-C)") (class "Default")
      (node (ref "LED_PWR") (pin "K") (pinfunction "C_K") (pintype "passive"))
      (node (ref "R57") (pin "P$2") (pinfunction "2_P$2") (pintype "bidirectional"))
    )
    (net (code "68") (name "Net-(OA7A-OUTA)") (class "Default")
      (node (ref "OA7") (pin "1") (pinfunction "OUTA_1") (pintype "bidirectional"))
      (node (ref "R13") (pin "P$1") (pinfunction "1_P$1") (pintype "bidirectional"))
    )
    (net (code "69") (name "Net-(OA10A-OUTA)") (class "Default")
      (node (ref "OA10") (pin "1") (pinfunction "OUTA_1") (pintype "bidirectional"))
      (node (ref "R35") (pin "P$1") (pinfunction "1_P$1") (pintype "bidirectional"))
      (node (ref "U$10") (pin "6") (pinfunction "6_6") (pintype "bidirectional"))
    )
    (net (code "70") (name "Net-(OA10B-OUTB)") (class "Default")
      (node (ref "OA10") (pin "7") (pinfunction "OUTB_7") (pintype "bidirectional"))
      (node (ref "R37") (pin "P$1") (pinfunction "1_P$1") (pintype "bidirectional"))
      (node (ref "U$10") (pin "3") (pinfunction "3_3") (pintype "bidirectional"))
    )
    (net (code "71") (name "Net-(OA11A-IN-)") (class "Default")
      (node (ref "OA11") (pin "2") (pinfunction "IN-_2") (pintype "bidirectional"))
      (node (ref "R36") (pin "P$1") (pinfunction "1_P$1") (pintype "bidirectional"))
      (node (ref "R65") (pin "P$2") (pinfunction "2_P$2") (pintype "bidirectional"))
    )
    (net (code "72") (name "Net-(OA11A-OUT)") (class "Default")
      (node (ref "OA11") (pin "13") (pinfunction "OUT_13") (pintype "bidirectional"))
      (node (ref "R49") (pin "1") (pinfunction "1_1") (pintype "bidirectional"))
      (node (ref "R65") (pin "P$1") (pinfunction "1_P$1") (pintype "bidirectional"))
    )
    (net (code "73") (name "Net-(OA11B-IN-)") (class "Default")
      (node (ref "OA11") (pin "6") (pinfunction "IN-_6") (pintype "bidirectional"))
      (node (ref "R34") (pin "P$1") (pinfunction "1_P$1") (pintype "bidirectional"))
      (node (ref "R66") (pin "P$2") (pinfunction "2_P$2") (pintype "bidirectional"))
    )
    (net (code "74") (name "Net-(OA11B-OUT)") (class "Default")
      (node (ref "OA11") (pin "9") (pinfunction "OUT_9") (pintype "bidirectional"))
      (node (ref "R48") (pin "2") (pinfunction "2_2") (pintype "bidirectional"))
      (node (ref "R66") (pin "P$1") (pinfunction "1_P$1") (pintype "bidirectional"))
    )
    (net (code "75") (name "Net-(OA12A-IN-)") (class "Default")
      (node (ref "OA12") (pin "2") (pinfunction "IN-_2") (pintype "bidirectional"))
      (node (ref "R42") (pin "P$1") (pinfunction "1_P$1") (pintype "bidirectional"))
      (node (ref "R44") (pin "P$2") (pinfunction "2_P$2") (pintype "bidirectional"))
    )
    (net (code "76") (name "Net-(OA12A-OUT)") (class "Default")
      (node (ref "OA12") (pin "13") (pinfunction "OUT_13") (pintype "bidirectional"))
      (node (ref "R44") (pin "P$1") (pinfunction "1_P$1") (pintype "bidirectional"))
      (node (ref "R46") (pin "2") (pinfunction "2_2") (pintype "bidirectional"))
    )
    (net (code "77") (name "Net-(OA12B-IN-)") (class "Default")
      (node (ref "OA12") (pin "6") (pinfunction "IN-_6") (pintype "bidirectional"))
      (node (ref "R43") (pin "P$1") (pinfunction "1_P$1") (pintype "bidirectional"))
      (node (ref "R45") (pin "P$2") (pinfunction "2_P$2") (pintype "bidirectional"))
    )
    (net (code "78") (name "Net-(OA12B-OUT)") (class "Default")
      (node (ref "OA12") (pin "9") (pinfunction "OUT_9") (pintype "bidirectional"))
      (node (ref "R45") (pin "P$1") (pinfunction "1_P$1") (pintype "bidirectional"))
      (node (ref "R47") (pin "1") (pinfunction "1_1") (pintype "bidirectional"))
    )
    (net (code "79") (name "Net-(R1-2)") (class "Default")
      (node (ref "R1") (pin "P$2") (pinfunction "2_P$2") (pintype "bidirectional"))
      (node (ref "R2") (pin "P$1") (pinfunction "1_P$1") (pintype "bidirectional"))
    )
    (net (code "80") (name "Net-(R4-2)") (class "Default")
      (node (ref "R4") (pin "P$2") (pinfunction "2_P$2") (pintype "bidirectional"))
      (node (ref "R5") (pin "P$1") (pinfunction "1_P$1") (pintype "bidirectional"))
    )
    (net (code "81") (name "Net-(R7-2)") (class "Default")
      (node (ref "R7") (pin "P$2") (pinfunction "2_P$2") (pintype "bidirectional"))
      (node (ref "R8") (pin "P$1") (pinfunction "1_P$1") (pintype "bidirectional"))
    )
    (net (code "82") (name "Net-(R10-2)") (class "Default")
      (node (ref "R10") (pin "P$2") (pinfunction "2_P$2") (pintype "bidirectional"))
      (node (ref "R11") (pin "P$1") (pinfunction "1_P$1") (pintype "bidirectional"))
    )
    (net (code "83") (name "Net-(R17-2)") (class "Default")
      (node (ref "R17") (pin "P$2") (pinfunction "2_P$2") (pintype "bidirectional"))
      (node (ref "U$3") (pin "15") (pinfunction "DT_15") (pintype "bidirectional"))
    )
    (net (code "84") (name "Net-(R18-1)") (class "Default")
      (node (ref "R18") (pin "P$1") (pinfunction "1_P$1") (pintype "bidirectional"))
      (node (ref "U$3") (pin "23") (pinfunction "D+_23") (pintype "bidirectional"))
    )
    (net (code "85") (name "Net-(R19-1)") (class "Default")
      (node (ref "R19") (pin "P$1") (pinfunction "1_P$1") (pintype "bidirectional"))
      (node (ref "U$3") (pin "22") (pinfunction "D-_22") (pintype "bidirectional"))
    )
    (net (code "86") (name "Net-(R34-2)") (class "Default")
      (node (ref "R34") (pin "P$2") (pinfunction "2_P$2") (pintype "bidirectional"))
      (node (ref "R36") (pin "P$2") (pinfunction "2_P$2") (pintype "bidirectional"))
      (node (ref "U$10") (pin "2") (pinfunction "2_2") (pintype "bidirectional"))
    )
    (net (code "87") (name "Net-(R42-2)") (class "Default")
      (node (ref "R42") (pin "P$2") (pinfunction "2_P$2") (pintype "bidirectional"))
      (node (ref "R43") (pin "P$2") (pinfunction "2_P$2") (pintype "bidirectional"))
      (node (ref "U$10") (pin "5") (pinfunction "5_5") (pintype "bidirectional"))
    )
    (net (code "88") (name "Net-(R54-2)") (class "Default")
      (node (ref "R54") (pin "P$2") (pinfunction "2_P$2") (pintype "bidirectional"))
      (node (ref "U1") (pin "20") (pinfunction "IREF_20") (pintype "output"))
    )
    (net (code "89") (name "Net-(R61-2)") (class "Default")
      (node (ref "R61") (pin "P$2") (pinfunction "2_P$2") (pintype "bidirectional"))
      (node (ref "S4") (pin "3") (pinfunction "3_3") (pintype "bidirectional"))
    )
    (net (code "90") (name "Net-(R62-2)") (class "Default")
      (node (ref "R62") (pin "P$2") (pinfunction "2_P$2") (pintype "bidirectional"))
      (node (ref "S4") (pin "1") (pinfunction "1_1") (pintype "bidirectional"))
    )
    (net (code "91") (name "Net-(R63-2)") (class "Default")
      (node (ref "R63") (pin "P$2") (pinfunction "2_P$2") (pintype "bidirectional"))
      (node (ref "S4") (pin "4") (pinfunction "4_4") (pintype "bidirectional"))
    )
    (net (code "92") (name "Net-(R64-2)") (class "Default")
      (node (ref "R64") (pin "P$2") (pinfunction "2_P$2") (pintype "bidirectional"))
      (node (ref "S4") (pin "6") (pinfunction "6_6") (pintype "bidirectional"))
    )
    (net (code "93") (name "Net-(U$3-VCOM)") (class "Default")
      (node (ref "C52") (pin "+") (pinfunction "+_+") (pintype "passive"))
      (node (ref "U$3") (pin "32") (pinfunction "VCOM_32") (pintype "bidirectional"))
    )
    (net (code "94") (name "Net-(U1-VCOML)") (class "Default")
      (node (ref "C88") (pin "-") (pinfunction "-_-") (pintype "passive"))
      (node (ref "U1") (pin "22") (pinfunction "VCOML_22") (pintype "input"))
    )
    (net (code "95") (name "Net-(U1-VCOMR)") (class "Default")
      (node (ref "C89") (pin "-") (pinfunction "-_-") (pintype "passive"))
      (node (ref "U1") (pin "21") (pinfunction "VCOMR_21") (pintype "input"))
    )
    (net (code "96") (name "VCC") (class "Default")
      (node (ref "C100") (pin "P$2") (pinfunction "2_P$2") (pintype "bidirectional"))
      (node (ref "C116") (pin "1") (pinfunction "1_1") (pintype "bidirectional"))
      (node (ref "C117") (pin "1") (pinfunction "1_1") (pintype "bidirectional"))
      (node (ref "C118") (pin "1") (pinfunction "1_1") (pintype "bidirectional"))
      (node (ref "C119") (pin "1") (pinfunction "1_1") (pintype "bidirectional"))
      (node (ref "C2") (pin "1") (pinfunction "1_1") (pintype "bidirectional"))
      (node (ref "C28") (pin "P$1") (pinfunction "1_P$1") (pintype "bidirectional"))
      (node (ref "C29") (pin "P$1") (pinfunction "1_P$1") (pintype "bidirectional"))
      (node (ref "C34") (pin "P$1") (pinfunction "1_P$1") (pintype "bidirectional"))
      (node (ref "C35") (pin "P$1") (pinfunction "1_P$1") (pintype "bidirectional"))
      (node (ref "C36") (pin "P$1") (pinfunction "1_P$1") (pintype "bidirectional"))
      (node (ref "C37") (pin "P$1") (pinfunction "1_P$1") (pintype "bidirectional"))
      (node (ref "C44") (pin "P$1") (pinfunction "1_P$1") (pintype "bidirectional"))
      (node (ref "C47") (pin "P$1") (pinfunction "1_P$1") (pintype "bidirectional"))
      (node (ref "C70") (pin "+") (pinfunction "+_+") (pintype "passive"))
      (node (ref "C72") (pin "+") (pinfunction "+_+") (pintype "passive"))
      (node (ref "C91") (pin "+") (pinfunction "+_+") (pintype "passive"))
      (node (ref "C93") (pin "2") (pinfunction "2_2") (pintype "passive"))
      (node (ref "OA10") (pin "8") (pinfunction "V+_8") (pintype "power_in"))
      (node (ref "OA11") (pin "14") (pinfunction "V+_14") (pintype "bidirectional"))
      (node (ref "OA11") (pin "8") (pinfunction "V+_8") (pintype "bidirectional"))
      (node (ref "OA12") (pin "14") (pinfunction "V+_14") (pintype "bidirectional"))
      (node (ref "OA12") (pin "8") (pinfunction "V+_8") (pintype "bidirectional"))
      (node (ref "OA7") (pin "8") (pinfunction "V+_8") (pintype "power_in"))
      (node (ref "OA8") (pin "8") (pinfunction "V+_8") (pintype "power_in"))
      (node (ref "OA9") (pin "8") (pinfunction "V+_8") (pintype "power_in"))
      (node (ref "R1") (pin "P$1") (pinfunction "1_P$1") (pintype "bidirectional"))
      (node (ref "U$1") (pin "1") (pinfunction "OUT_1") (pintype "bidirectional"))
      (node (ref "U$1") (pin "20") (pinfunction "OUT_20") (pintype "bidirectional"))
    )
    (net (code "97") (name "VEE") (class "Default")
      (node (ref "C101") (pin "P$2") (pinfunction "2_P$2") (pintype "bidirectional"))
      (node (ref "C30") (pin "P$1") (pinfunction "1_P$1") (pintype "bidirectional"))
      (node (ref "C31") (pin "P$1") (pinfunction "1_P$1") (pintype "bidirectional"))
      (node (ref "C32") (pin "P$1") (pinfunction "1_P$1") (pintype "bidirectional"))
      (node (ref "C33") (pin "P$1") (pinfunction "1_P$1") (pintype "bidirectional"))
      (node (ref "C38") (pin "P$1") (pinfunction "1_P$1") (pintype "bidirectional"))
      (node (ref "C39") (pin "P$1") (pinfunction "1_P$1") (pintype "bidirectional"))
      (node (ref "C4") (pin "1") (pinfunction "1_1") (pintype "bidirectional"))
      (node (ref "C45") (pin "P$1") (pinfunction "1_P$1") (pintype "bidirectional"))
      (node (ref "C46") (pin "P$1") (pinfunction "1_P$1") (pintype "bidirectional"))
      (node (ref "C71") (pin "-") (pinfunction "-_-") (pintype "passive"))
      (node (ref "C73") (pin "-") (pinfunction "-_-") (pintype "passive"))
      (node (ref "C92") (pin "-") (pinfunction "-_-") (pintype "passive"))
      (node (ref "C94") (pin "1") (pinfunction "1_1") (pintype "passive"))
      (node (ref "OA10") (pin "4") (pinfunction "V-_4") (pintype "power_in"))
      (node (ref "OA11") (pin "10") (pinfunction "V-_10") (pintype "bidirectional"))
      (node (ref "OA11") (pin "12") (pinfunction "V-_12") (pintype "bidirectional"))
      (node (ref "OA12") (pin "10") (pinfunction "V-_10") (pintype "bidirectional"))
      (node (ref "OA12") (pin "12") (pinfunction "V-_12") (pintype "bidirectional"))
      (node (ref "OA7") (pin "4") (pinfunction "V-_4") (pintype "power_in"))
      (node (ref "OA8") (pin "4") (pinfunction "V-_4") (pintype "power_in"))
      (node (ref "OA9") (pin "4") (pinfunction "V-_4") (pintype "power_in"))
      (node (ref "R4") (pin "P$1") (pinfunction "1_P$1") (pintype "bidirectional"))
      (node (ref "U$2") (pin "1") (pinfunction "OUT_1") (pintype "bidirectional"))
      (node (ref "U$2") (pin "20") (pinfunction "OUT2_20") (pintype "bidirectional"))
    )
    (net (code "98") (name "unconnected-(CN1-PadID)") (class "Default")
      (node (ref "CN1") (pin "ID") (pinfunction "ID_ID") (pintype "bidirectional"))
    )
    (net (code "99") (name "unconnected-(OA7-PadTP)") (class "Default")
      (node (ref "OA7") (pin "TP") (pinfunction "TP_TP") (pintype "bidirectional"))
    )
    (net (code "100") (name "unconnected-(OA8-PadTP)") (class "Default")
      (node (ref "OA8") (pin "TP") (pinfunction "TP_TP") (pintype "bidirectional"))
    )
    (net (code "101") (name "unconnected-(OA9-PadTP)") (class "Default")
      (node (ref "OA9") (pin "TP") (pinfunction "TP_TP") (pintype "bidirectional"))
    )
    (net (code "102") (name "unconnected-(OA10-PadTP)") (class "Default")
      (node (ref "OA10") (pin "TP") (pinfunction "TP_TP") (pintype "bidirectional"))
    )
    (net (code "103") (name "unconnected-(OA11-PadTP)") (class "Default")
      (node (ref "OA11") (pin "TP") (pinfunction "TP_TP") (pintype "bidirectional"))
    )
    (net (code "104") (name "unconnected-(OA12-PadTP)") (class "Default")
      (node (ref "OA12") (pin "TP") (pinfunction "TP_TP") (pintype "bidirectional"))
    )
    (net (code "105") (name "unconnected-(S2-Pad1)") (class "Default")
      (node (ref "S2") (pin "1") (pinfunction "1_1") (pintype "bidirectional"))
    )
    (net (code "106") (name "unconnected-(S2-Pad4)") (class "Default")
      (node (ref "S2") (pin "4") (pinfunction "4_4") (pintype "bidirectional"))
    )
    (net (code "107") (name "unconnected-(U$1-0P1V-Pad12)") (class "Default")
      (node (ref "U$1") (pin "12") (pinfunction "0P1V_12") (pintype "bidirectional"))
    )
    (net (code "108") (name "unconnected-(U$1-0P2V-Pad11)") (class "Default")
      (node (ref "U$1") (pin "11") (pinfunction "0P2V_11") (pintype "bidirectional"))
    )
    (net (code "109") (name "unconnected-(U$1-0P4V-Pad10)") (class "Default")
      (node (ref "U$1") (pin "10") (pinfunction "0P4V_10") (pintype "bidirectional"))
    )
    (net (code "110") (name "unconnected-(U$1-0P8V-Pad9)") (class "Default")
      (node (ref "U$1") (pin "9") (pinfunction "0P8V_9") (pintype "bidirectional"))
    )
    (net (code "111") (name "unconnected-(U$1-1P6V-Pad8)") (class "Default")
      (node (ref "U$1") (pin "8") (pinfunction "1P6V_8") (pintype "bidirectional"))
    )
    (net (code "112") (name "unconnected-(U$1-3P2V-Pad6)") (class "Default")
      (node (ref "U$1") (pin "6") (pinfunction "3P2V_6") (pintype "bidirectional"))
    )
    (net (code "113") (name "unconnected-(U$1-6P4V1-Pad5)") (class "Default")
      (node (ref "U$1") (pin "5") (pinfunction "6P4V1_5") (pintype "bidirectional"))
    )
    (net (code "114") (name "unconnected-(U$1-6P4V2-Pad4)") (class "Default")
      (node (ref "U$1") (pin "4") (pinfunction "6P4V2_4") (pintype "bidirectional"))
    )
    (net (code "115") (name "unconnected-(U$1-NC-Pad2)") (class "Default")
      (node (ref "U$1") (pin "2") (pinfunction "NC_2") (pintype "bidirectional"))
    )
    (net (code "116") (name "unconnected-(U$1-NC-Pad17)") (class "Default")
      (node (ref "U$1") (pin "17") (pinfunction "NC_17") (pintype "bidirectional"))
    )
    (net (code "117") (name "unconnected-(U$1-NC-Pad18)") (class "Default")
      (node (ref "U$1") (pin "18") (pinfunction "NC_18") (pintype "bidirectional"))
    )
    (net (code "118") (name "unconnected-(U$1-NC-Pad19)") (class "Default")
      (node (ref "U$1") (pin "19") (pinfunction "NC_19") (pintype "bidirectional"))
    )
    (net (code "119") (name "unconnected-(U$2-NC1-Pad2)") (class "Default")
      (node (ref "U$2") (pin "2") (pinfunction "NC1_2") (pintype "bidirectional"))
    )
    (net (code "120") (name "unconnected-(U$2-NC2-Pad4)") (class "Default")
      (node (ref "U$2") (pin "4") (pinfunction "NC2_4") (pintype "bidirectional"))
    )
    (net (code "121") (name "unconnected-(U$2-NC3-Pad5)") (class "Default")
      (node (ref "U$2") (pin "5") (pinfunction "NC3_5") (pintype "bidirectional"))
    )
    (net (code "122") (name "unconnected-(U$2-NC4-Pad6)") (class "Default")
      (node (ref "U$2") (pin "6") (pinfunction "NC4_6") (pintype "bidirectional"))
    )
    (net (code "123") (name "unconnected-(U$2-NC5-Pad8)") (class "Default")
      (node (ref "U$2") (pin "8") (pinfunction "NC5_8") (pintype "bidirectional"))
    )
    (net (code "124") (name "unconnected-(U$2-NC6-Pad9)") (class "Default")
      (node (ref "U$2") (pin "9") (pinfunction "NC6_9") (pintype "bidirectional"))
    )
    (net (code "125") (name "unconnected-(U$2-NC7-Pad10)") (class "Default")
      (node (ref "U$2") (pin "10") (pinfunction "NC7_10") (pintype "bidirectional"))
    )
    (net (code "126") (name "unconnected-(U$2-NC8-Pad11)") (class "Default")
      (node (ref "U$2") (pin "11") (pinfunction "NC8_11") (pintype "bidirectional"))
    )
    (net (code "127") (name "unconnected-(U$2-NC9-Pad12)") (class "Default")
      (node (ref "U$2") (pin "12") (pinfunction "NC9_12") (pintype "bidirectional"))
    )
    (net (code "128") (name "unconnected-(U$2-NC10-Pad17)") (class "Default")
      (node (ref "U$2") (pin "17") (pinfunction "NC10_17") (pintype "bidirectional"))
    )
    (net (code "129") (name "unconnected-(U$2-NC11-Pad18)") (class "Default")
      (node (ref "U$2") (pin "18") (pinfunction "NC11_18") (pintype "bidirectional"))
    )
    (net (code "130") (name "unconnected-(U$2-NC12-Pad19)") (class "Default")
      (node (ref "U$2") (pin "19") (pinfunction "NC12_19") (pintype "bidirectional"))
    )
    (net (code "131") (name "unconnected-(U$3-CK-Pad14)") (class "Default")
      (node (ref "U$3") (pin "14") (pinfunction "CK_14") (pintype "bidirectional"))
    )
    (net (code "132") (name "unconnected-(U$3-FUNC3-Pad4)") (class "Default")
      (node (ref "U$3") (pin "4") (pinfunction "FUNC3_4") (pintype "bidirectional"))
    )
    (net (code "133") (name "unconnected-(U$3-HID1{slash}MC-Pad7)") (class "Default")
      (node (ref "U$3") (pin "7") (pinfunction "HID1/MC_7") (pintype "bidirectional"))
    )
    (net (code "134") (name "unconnected-(U$3-HID2{slash}MD-Pad8)") (class "Default")
      (node (ref "U$3") (pin "8") (pinfunction "HID2/MD_8") (pintype "bidirectional"))
    )
    (net (code "135") (name "unconnected-(U$3-HIDO{slash}MS-Pad6)") (class "Default")
      (node (ref "U$3") (pin "6") (pinfunction "HIDO/MS_6") (pintype "bidirectional"))
    )
    (net (code "136") (name "unconnected-(U$3-SSPND\\-Pad11)") (class "Default")
      (node (ref "U$3") (pin "11") (pinfunction "SSPND\\_11") (pintype "bidirectional"))
    )
    (net (code "137") (name "unconnected-(U$3-VOUTL-Pad28)") (class "Default")
      (node (ref "U$3") (pin "28") (pinfunction "VOUTL_28") (pintype "bidirectional"))
    )
    (net (code "138") (name "unconnected-(U$3-VOUTR-Pad29)") (class "Default")
      (node (ref "U$3") (pin "29") (pinfunction "VOUTR_29") (pintype "bidirectional"))
    )
    (net (code "139") (name "unconnected-(U$6-0P1V-Pad12)") (class "Default")
      (node (ref "U$6") (pin "12") (pinfunction "0P1V_12") (pintype "bidirectional"))
    )
    (net (code "140") (name "unconnected-(U$6-0P2V-Pad11)") (class "Default")
      (node (ref "U$6") (pin "11") (pinfunction "0P2V_11") (pintype "bidirectional"))
    )
    (net (code "141") (name "unconnected-(U$6-0P4V-Pad10)") (class "Default")
      (node (ref "U$6") (pin "10") (pinfunction "0P4V_10") (pintype "bidirectional"))
    )
    (net (code "142") (name "unconnected-(U$6-0P8V-Pad9)") (class "Default")
      (node (ref "U$6") (pin "9") (pinfunction "0P8V_9") (pintype "bidirectional"))
    )
    (net (code "143") (name "unconnected-(U$6-1P6V-Pad8)") (class "Default")
      (node (ref "U$6") (pin "8") (pinfunction "1P6V_8") (pintype "bidirectional"))
    )
    (net (code "144") (name "unconnected-(U$6-3P2V-Pad6)") (class "Default")
      (node (ref "U$6") (pin "6") (pinfunction "3P2V_6") (pintype "bidirectional"))
    )
    (net (code "145") (name "unconnected-(U$6-6P4V1-Pad5)") (class "Default")
      (node (ref "U$6") (pin "5") (pinfunction "6P4V1_5") (pintype "bidirectional"))
    )
    (net (code "146") (name "unconnected-(U$6-6P4V2-Pad4)") (class "Default")
      (node (ref "U$6") (pin "4") (pinfunction "6P4V2_4") (pintype "bidirectional"))
    )
    (net (code "147") (name "unconnected-(U$6-NC-Pad2)") (class "Default")
      (node (ref "U$6") (pin "2") (pinfunction "NC_2") (pintype "bidirectional"))
    )
    (net (code "148") (name "unconnected-(U$6-NC-Pad17)") (class "Default")
      (node (ref "U$6") (pin "17") (pinfunction "NC_17") (pintype "bidirectional"))
    )
    (net (code "149") (name "unconnected-(U$6-NC-Pad18)") (class "Default")
      (node (ref "U$6") (pin "18") (pinfunction "NC_18") (pintype "bidirectional"))
    )
    (net (code "150") (name "unconnected-(U$6-NC-Pad19)") (class "Default")
      (node (ref "U$6") (pin "19") (pinfunction "NC_19") (pintype "bidirectional"))
    )
    (net (code "151") (name "unconnected-(U$7-0P1V-Pad12)") (class "Default")
      (node (ref "U$7") (pin "12") (pinfunction "0P1V_12") (pintype "bidirectional"))
    )
    (net (code "152") (name "unconnected-(U$7-0P2V-Pad11)") (class "Default")
      (node (ref "U$7") (pin "11") (pinfunction "0P2V_11") (pintype "bidirectional"))
    )
    (net (code "153") (name "unconnected-(U$7-0P4V-Pad10)") (class "Default")
      (node (ref "U$7") (pin "10") (pinfunction "0P4V_10") (pintype "bidirectional"))
    )
    (net (code "154") (name "unconnected-(U$7-0P8V-Pad9)") (class "Default")
      (node (ref "U$7") (pin "9") (pinfunction "0P8V_9") (pintype "bidirectional"))
    )
    (net (code "155") (name "unconnected-(U$7-1P6V-Pad8)") (class "Default")
      (node (ref "U$7") (pin "8") (pinfunction "1P6V_8") (pintype "bidirectional"))
    )
    (net (code "156") (name "unconnected-(U$7-3P2V-Pad6)") (class "Default")
      (node (ref "U$7") (pin "6") (pinfunction "3P2V_6") (pintype "bidirectional"))
    )
    (net (code "157") (name "unconnected-(U$7-6P4V1-Pad5)") (class "Default")
      (node (ref "U$7") (pin "5") (pinfunction "6P4V1_5") (pintype "bidirectional"))
    )
    (net (code "158") (name "unconnected-(U$7-6P4V2-Pad4)") (class "Default")
      (node (ref "U$7") (pin "4") (pinfunction "6P4V2_4") (pintype "bidirectional"))
    )
    (net (code "159") (name "unconnected-(U$7-NC-Pad2)") (class "Default")
      (node (ref "U$7") (pin "2") (pinfunction "NC_2") (pintype "bidirectional"))
    )
    (net (code "160") (name "unconnected-(U$7-NC-Pad17)") (class "Default")
      (node (ref "U$7") (pin "17") (pinfunction "NC_17") (pintype "bidirectional"))
    )
    (net (code "161") (name "unconnected-(U$7-NC-Pad18)") (class "Default")
      (node (ref "U$7") (pin "18") (pinfunction "NC_18") (pintype "bidirectional"))
    )
    (net (code "162") (name "unconnected-(U$7-NC-Pad19)") (class "Default")
      (node (ref "U$7") (pin "19") (pinfunction "NC_19") (pintype "bidirectional"))
    )
    (net (code "163") (name "unconnected-(U1-ZERO-Pad13)") (class "Default")
      (node (ref "U1") (pin "13") (pinfunction "ZERO_13") (pintype "output"))
    )
    (net (code "164") (name "unconnected-(X2-Pad3)") (class "Default")
      (node (ref "X2") (pin "3") (pinfunction "3_3") (pintype "passive"))
    )
    (net (code "165") (name "unconnected-(X2-Pad4)") (class "Default")
      (node (ref "X2") (pin "4") (pinfunction "4_4") (pintype "passive"))
    )
  )
)
